# Gate_Drives.net
KiCad netlist of a schematic drawn in Altium Designer
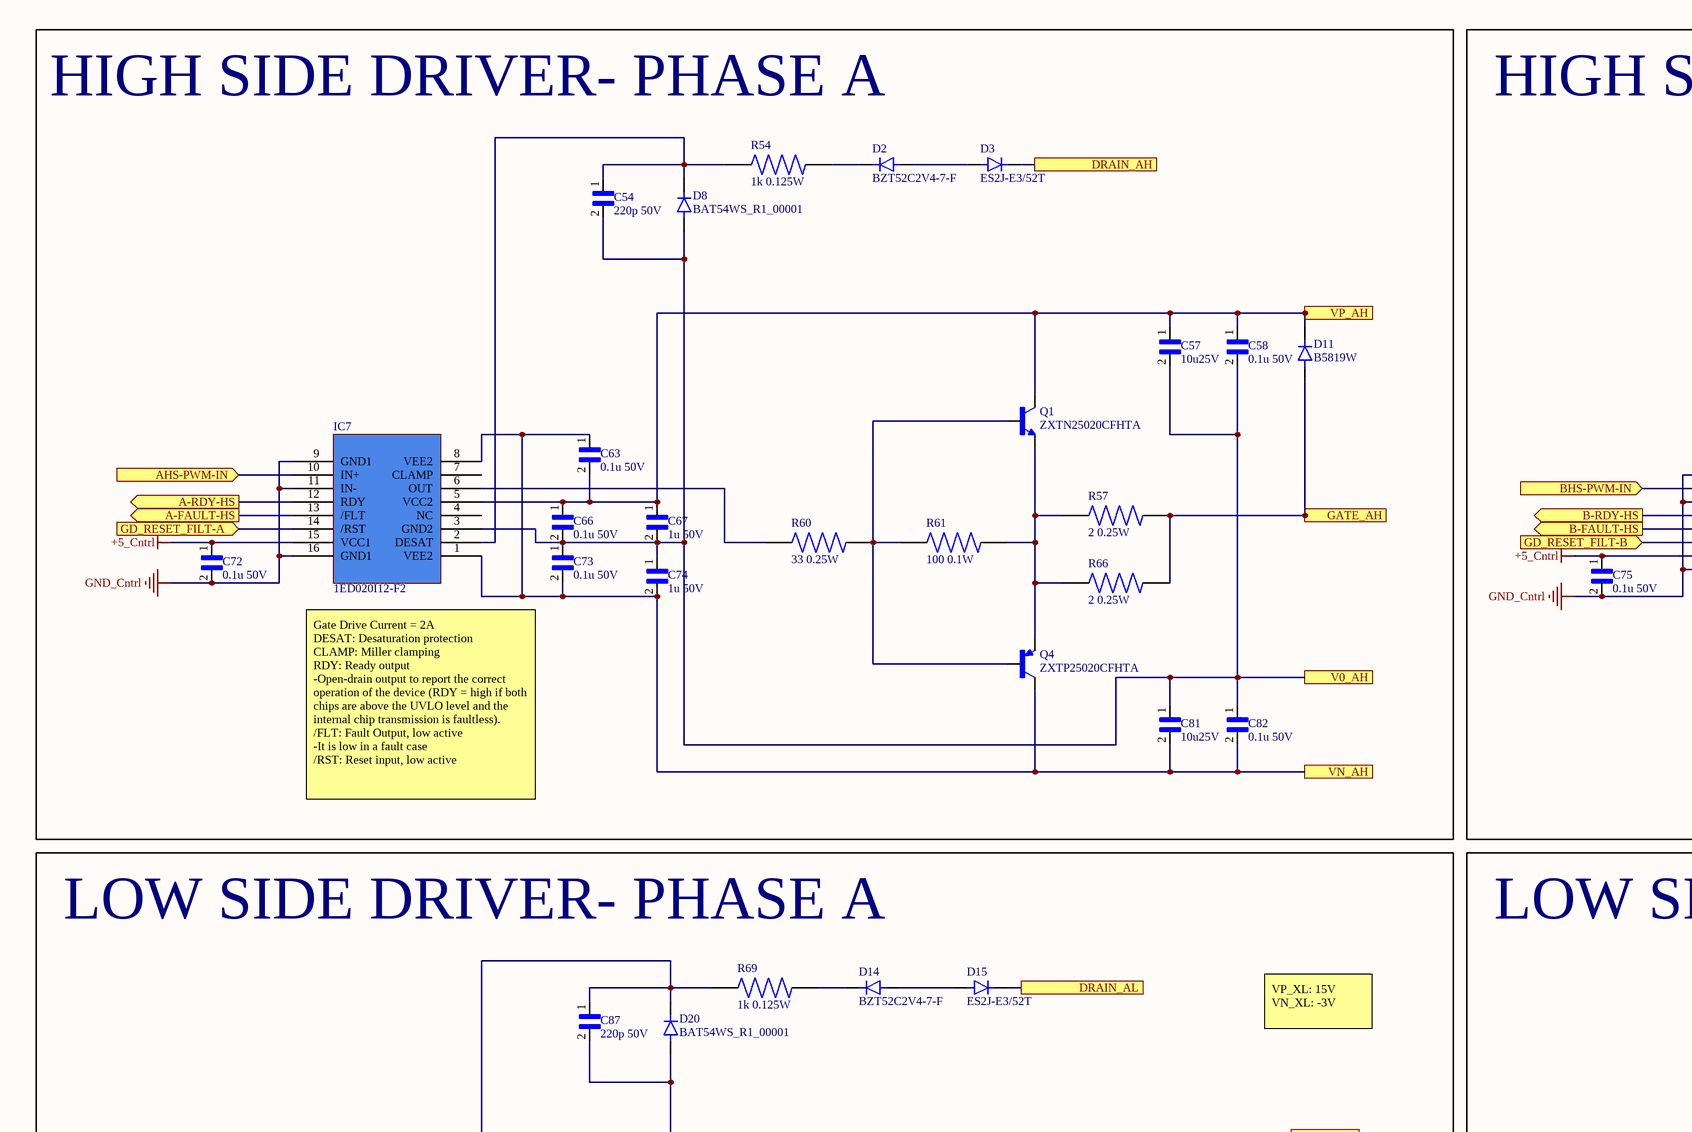
[diagram p0: Gate Drives.SchDoc, top left]
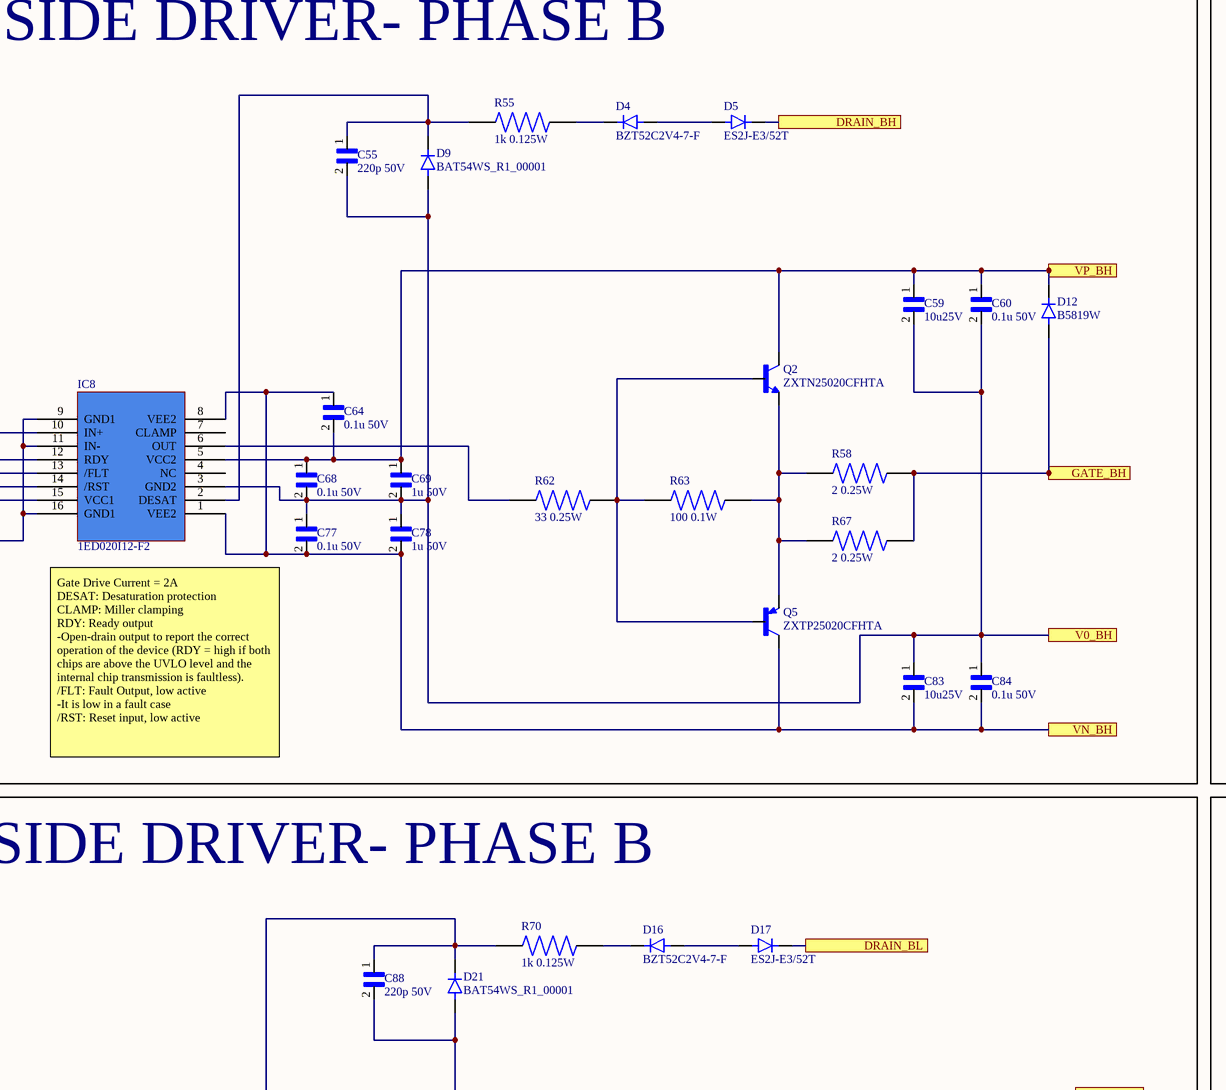
[diagram p1: Gate Drives.SchDoc, top middle]
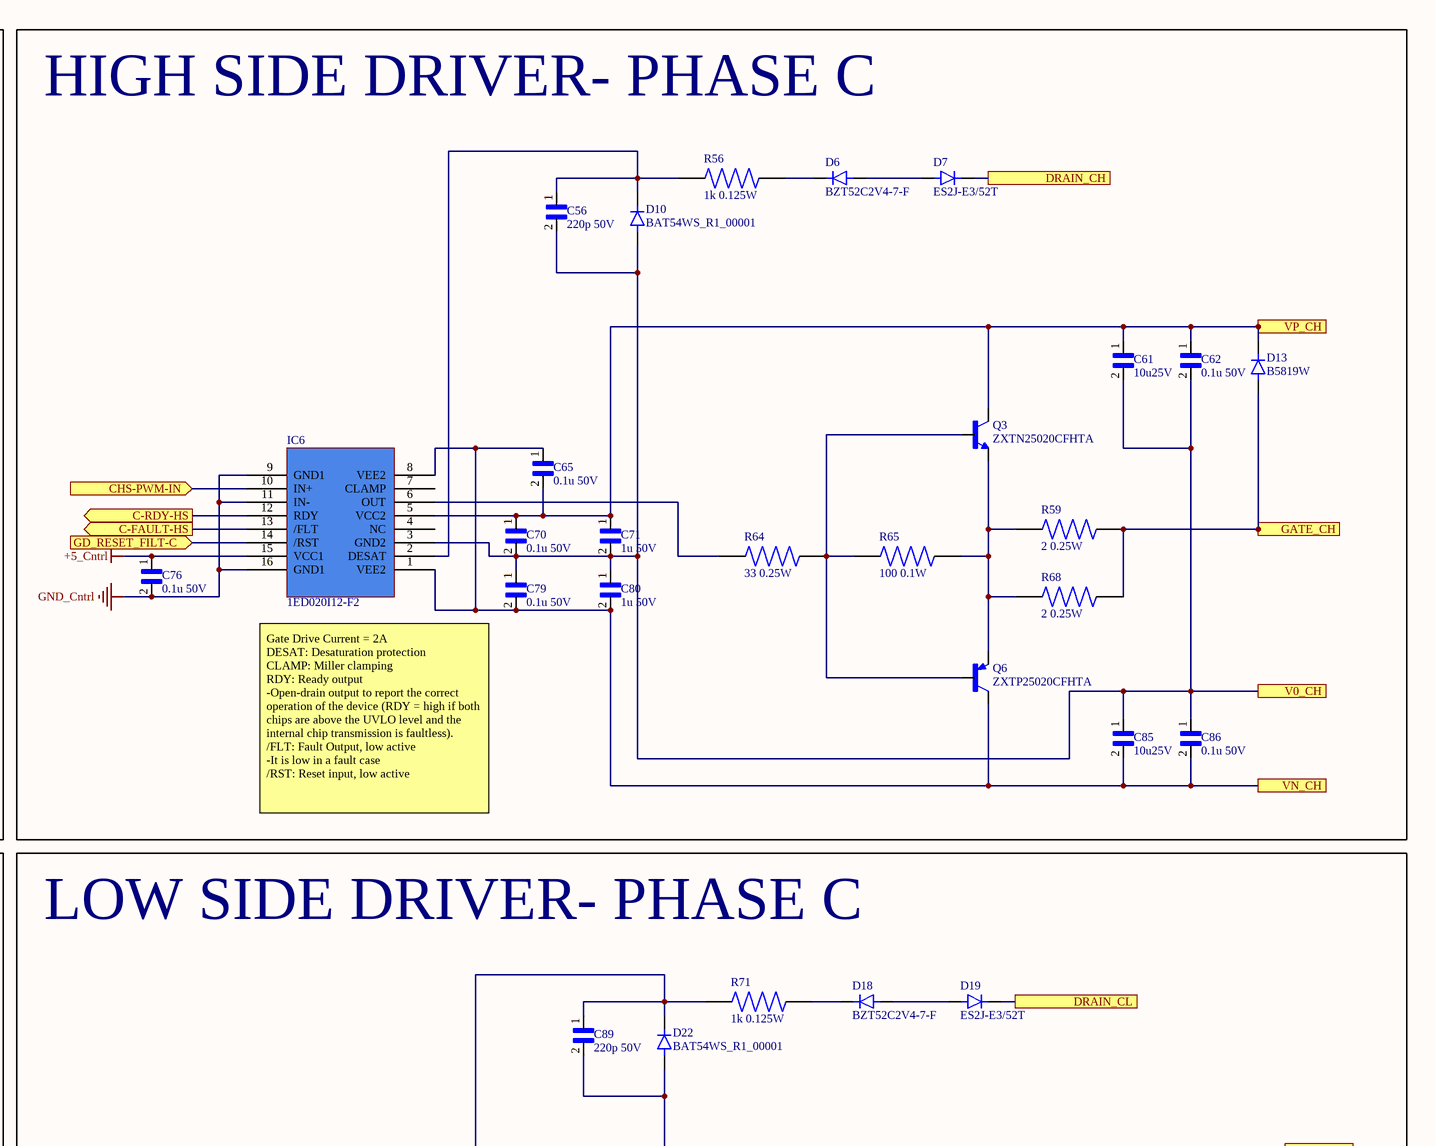
[diagram p2: Gate Drives.SchDoc, top right]
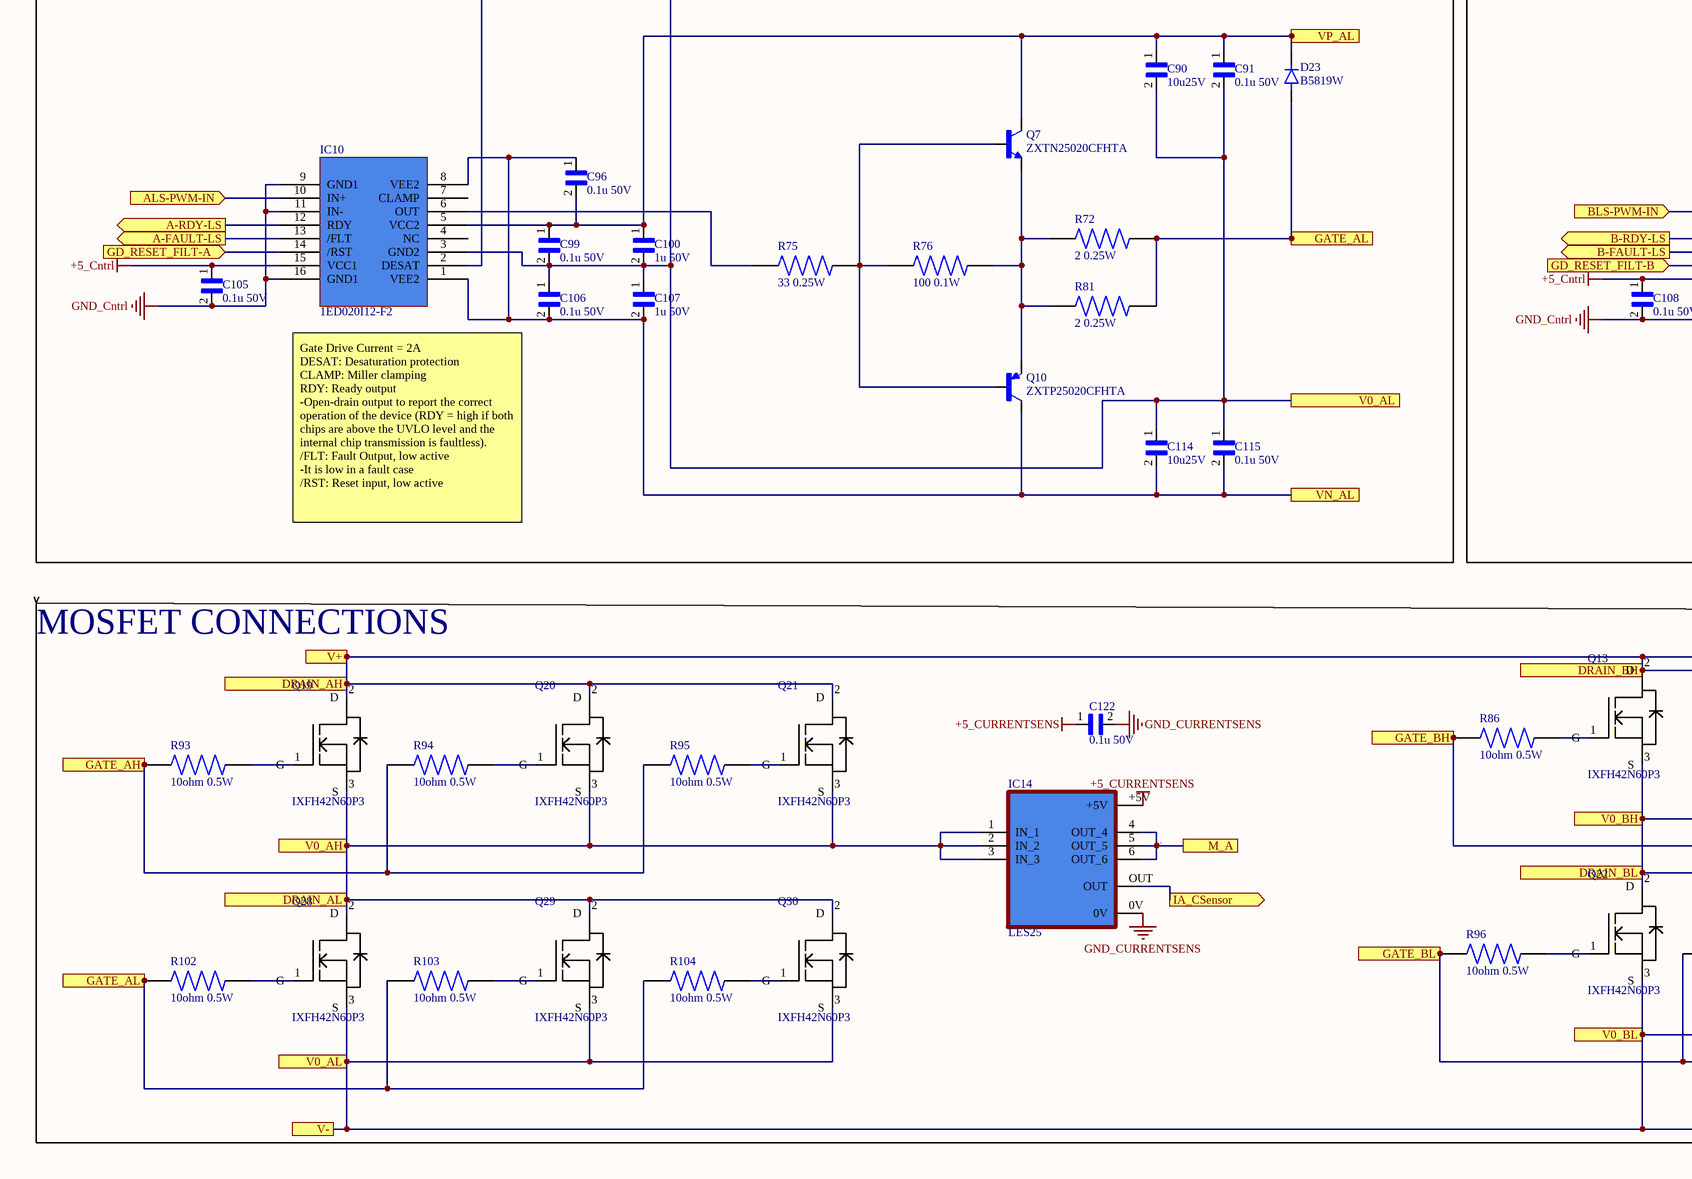
[diagram p3: Gate Drives.SchDoc, bottom left]
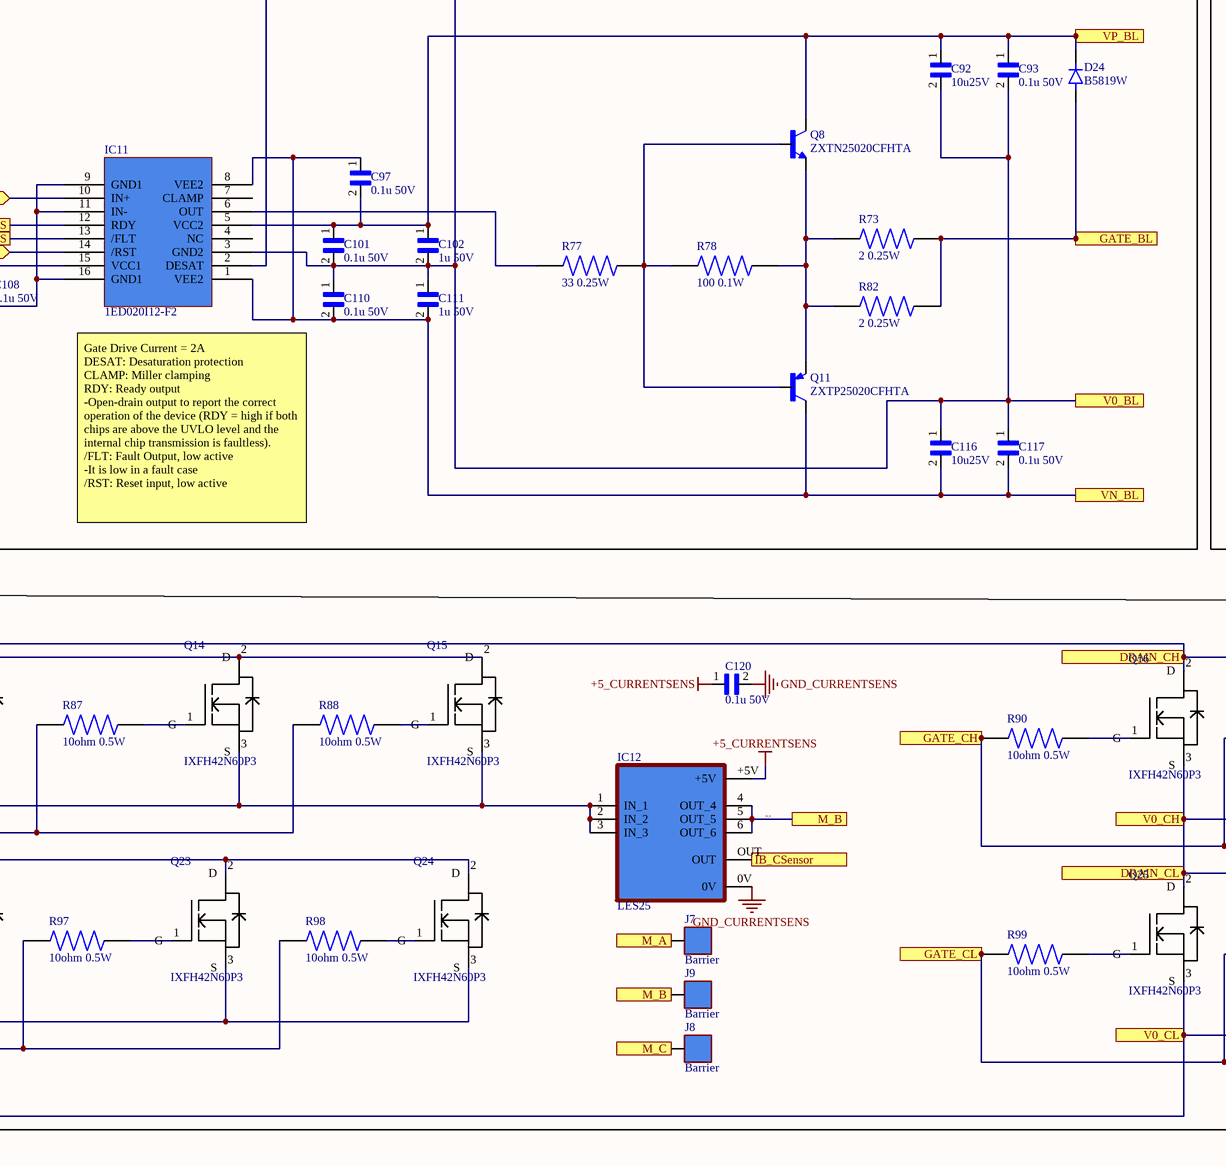
[diagram p4: Gate Drives.SchDoc, bottom middle]
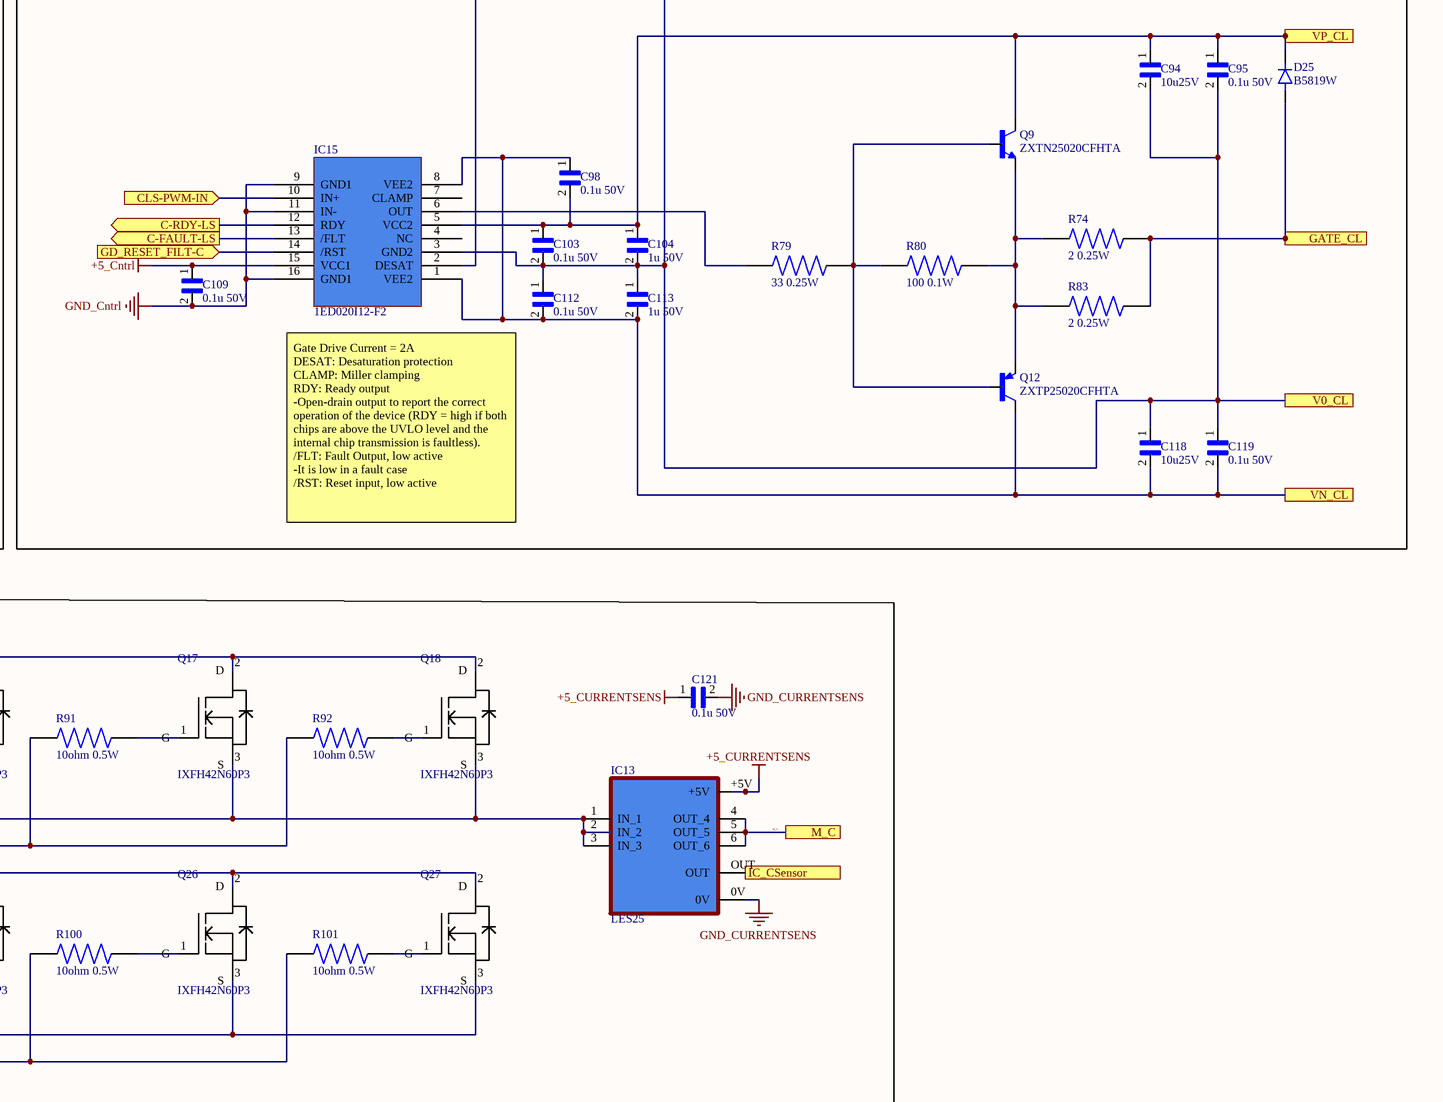
[diagram p5: Gate Drives.SchDoc, bottom right]

(export (version "E")
  (design (tool "Eeschema 10.0.6"))
  (components
    (comp (ref "C54") (value "220p 50V") (footprint "CAP0805") (libsource (lib "CAP0805") (part "CAP0805")))
    (comp (ref "C55") (value "220p 50V") (footprint "CAP0805") (libsource (lib "CAP0805") (part "CAP0805")))
    (comp (ref "C56") (value "220p 50V") (footprint "CAP0805") (libsource (lib "CAP0805") (part "CAP0805")))
    (comp (ref "C57") (value "10u25V") (footprint "CAP0805") (libsource (lib "CAP0805") (part "CAP0805")))
    (comp (ref "C58") (value "0.1u 50V") (footprint "CAP0805") (libsource (lib "CAP0805") (part "CAP0805")))
    (comp (ref "C59") (value "10u25V") (footprint "CAP0805") (libsource (lib "CAP0805") (part "CAP0805")))
    (comp (ref "C60") (value "0.1u 50V") (footprint "CAP0805") (libsource (lib "CAP0805") (part "CAP0805")))
    (comp (ref "C61") (value "10u25V") (footprint "CAP0805") (libsource (lib "CAP0805") (part "CAP0805")))
    (comp (ref "C62") (value "0.1u 50V") (footprint "CAP0805") (libsource (lib "CAP0805") (part "CAP0805")))
    (comp (ref "C63") (value "0.1u 50V") (footprint "CAP0805") (libsource (lib "CAP0805") (part "CAP0805")))
    (comp (ref "C64") (value "0.1u 50V") (footprint "CAP0805") (libsource (lib "CAP0805") (part "CAP0805")))
    (comp (ref "C65") (value "0.1u 50V") (footprint "CAP0805") (libsource (lib "CAP0805") (part "CAP0805")))
    (comp (ref "C66") (value "0.1u 50V") (footprint "CAP0805") (libsource (lib "CAP0805") (part "CAP0805")))
    (comp (ref "C67") (value "1u 50V") (footprint "CAP0805") (libsource (lib "CAP0805") (part "CAP0805")))
    (comp (ref "C68") (value "0.1u 50V") (footprint "CAP0805") (libsource (lib "CAP0805") (part "CAP0805")))
    (comp (ref "C69") (value "1u 50V") (footprint "CAP0805") (libsource (lib "CAP0805") (part "CAP0805")))
    (comp (ref "C70") (value "0.1u 50V") (footprint "CAP0805") (libsource (lib "CAP0805") (part "CAP0805")))
    (comp (ref "C71") (value "1u 50V") (footprint "CAP0805") (libsource (lib "CAP0805") (part "CAP0805")))
    (comp (ref "C72") (value "0.1u 50V") (footprint "CAP0805") (libsource (lib "CAP0805") (part "CAP0805")))
    (comp (ref "C73") (value "0.1u 50V") (footprint "CAP0805") (libsource (lib "CAP0805") (part "CAP0805")))
    (comp (ref "C74") (value "1u 50V") (footprint "CAP0805") (libsource (lib "CAP0805") (part "CAP0805")))
    (comp (ref "C75") (value "0.1u 50V") (footprint "CAP0805") (libsource (lib "CAP0805") (part "CAP0805")))
    (comp (ref "C76") (value "0.1u 50V") (footprint "CAP0805") (libsource (lib "CAP0805") (part "CAP0805")))
    (comp (ref "C77") (value "0.1u 50V") (footprint "CAP0805") (libsource (lib "CAP0805") (part "CAP0805")))
    (comp (ref "C78") (value "1u 50V") (footprint "CAP0805") (libsource (lib "CAP0805") (part "CAP0805")))
    (comp (ref "C79") (value "0.1u 50V") (footprint "CAP0805") (libsource (lib "CAP0805") (part "CAP0805")))
    (comp (ref "C80") (value "1u 50V") (footprint "CAP0805") (libsource (lib "CAP0805") (part "CAP0805")))
    (comp (ref "C81") (value "10u25V") (footprint "CAP0805") (libsource (lib "CAP0805") (part "CAP0805")))
    (comp (ref "C82") (value "0.1u 50V") (footprint "CAP0805") (libsource (lib "CAP0805") (part "CAP0805")))
    (comp (ref "C83") (value "10u25V") (footprint "CAP0805") (libsource (lib "CAP0805") (part "CAP0805")))
    (comp (ref "C84") (value "0.1u 50V") (footprint "CAP0805") (libsource (lib "CAP0805") (part "CAP0805")))
    (comp (ref "C85") (value "10u25V") (footprint "CAP0805") (libsource (lib "CAP0805") (part "CAP0805")))
    (comp (ref "C86") (value "0.1u 50V") (footprint "CAP0805") (libsource (lib "CAP0805") (part "CAP0805")))
    (comp (ref "C87") (value "220p 50V") (footprint "CAP0805") (libsource (lib "CAP0805") (part "CAP0805")))
    (comp (ref "C88") (value "220p 50V") (footprint "CAP0805") (libsource (lib "CAP0805") (part "CAP0805")))
    (comp (ref "C89") (value "220p 50V") (footprint "CAP0805") (libsource (lib "CAP0805") (part "CAP0805")))
    (comp (ref "C90") (value "10u25V") (footprint "CAP0805") (libsource (lib "CAP0805") (part "CAP0805")))
    (comp (ref "C91") (value "0.1u 50V") (footprint "CAP0805") (libsource (lib "CAP0805") (part "CAP0805")))
    (comp (ref "C92") (value "10u25V") (footprint "CAP0805") (libsource (lib "CAP0805") (part "CAP0805")))
    (comp (ref "C93") (value "0.1u 50V") (footprint "CAP0805") (libsource (lib "CAP0805") (part "CAP0805")))
    (comp (ref "C94") (value "10u25V") (footprint "CAP0805") (libsource (lib "CAP0805") (part "CAP0805")))
    (comp (ref "C95") (value "0.1u 50V") (footprint "CAP0805") (libsource (lib "CAP0805") (part "CAP0805")))
    (comp (ref "C96") (value "0.1u 50V") (footprint "CAP0805") (libsource (lib "CAP0805") (part "CAP0805")))
    (comp (ref "C97") (value "0.1u 50V") (footprint "CAP0805") (libsource (lib "CAP0805") (part "CAP0805")))
    (comp (ref "C98") (value "0.1u 50V") (footprint "CAP0805") (libsource (lib "CAP0805") (part "CAP0805")))
    (comp (ref "C99") (value "0.1u 50V") (footprint "CAP0805") (libsource (lib "CAP0805") (part "CAP0805")))
    (comp (ref "C100") (value "1u 50V") (footprint "CAP0805") (libsource (lib "CAP0805") (part "CAP0805")))
    (comp (ref "C101") (value "0.1u 50V") (footprint "CAP0805") (libsource (lib "CAP0805") (part "CAP0805")))
    (comp (ref "C102") (value "1u 50V") (footprint "CAP0805") (libsource (lib "CAP0805") (part "CAP0805")))
    (comp (ref "C103") (value "0.1u 50V") (footprint "CAP0805") (libsource (lib "CAP0805") (part "CAP0805")))
    (comp (ref "C104") (value "1u 50V") (footprint "CAP0805") (libsource (lib "CAP0805") (part "CAP0805")))
    (comp (ref "C105") (value "0.1u 50V") (footprint "CAP0805") (libsource (lib "CAP0805") (part "CAP0805")))
    (comp (ref "C106") (value "0.1u 50V") (footprint "CAP0805") (libsource (lib "CAP0805") (part "CAP0805")))
    (comp (ref "C107") (value "1u 50V") (footprint "CAP0805") (libsource (lib "CAP0805") (part "CAP0805")))
    (comp (ref "C108") (value "0.1u 50V") (footprint "CAP0805") (libsource (lib "CAP0805") (part "CAP0805")))
    (comp (ref "C109") (value "0.1u 50V") (footprint "CAP0805") (libsource (lib "CAP0805") (part "CAP0805")))
    (comp (ref "C110") (value "0.1u 50V") (footprint "CAP0805") (libsource (lib "CAP0805") (part "CAP0805")))
    (comp (ref "C111") (value "1u 50V") (footprint "CAP0805") (libsource (lib "CAP0805") (part "CAP0805")))
    (comp (ref "C112") (value "0.1u 50V") (footprint "CAP0805") (libsource (lib "CAP0805") (part "CAP0805")))
    (comp (ref "C113") (value "1u 50V") (footprint "CAP0805") (libsource (lib "CAP0805") (part "CAP0805")))
    (comp (ref "C114") (value "10u25V") (footprint "CAP0805") (libsource (lib "CAP0805") (part "CAP0805")))
    (comp (ref "C115") (value "0.1u 50V") (footprint "CAP0805") (libsource (lib "CAP0805") (part "CAP0805")))
    (comp (ref "C116") (value "10u25V") (footprint "CAP0805") (libsource (lib "CAP0805") (part "CAP0805")))
    (comp (ref "C117") (value "0.1u 50V") (footprint "CAP0805") (libsource (lib "CAP0805") (part "CAP0805")))
    (comp (ref "C118") (value "10u25V") (footprint "CAP0805") (libsource (lib "CAP0805") (part "CAP0805")))
    (comp (ref "C119") (value "0.1u 50V") (footprint "CAP0805") (libsource (lib "CAP0805") (part "CAP0805")))
    (comp (ref "C120") (value "0.1u 50V") (footprint "CAP0805") (libsource (lib "") (part "CAP0805_1")))
    (comp (ref "C121") (value "0.1u 50V") (footprint "CAP0805") (libsource (lib "") (part "CAP0805_1")))
    (comp (ref "C122") (value "0.1u 50V") (footprint "CAP0805") (libsource (lib "") (part "CAP0805_1")))
    (comp (ref "D2")
      (value "BZT52C2V4-7-F")
      (footprint "BZT52C2V4-7-F")
      (libsource (lib "BZT52C2V4-7-F") (part "BZT52C2V4-7-F"))
    )
    (comp (ref "D3")
      (value "ES2J-E3/52T")
      (footprint "ES2J-E3/52T")
      (libsource (lib "ES2J-E3 52T") (part "ES2J-E3/52T"))
    )
    (comp (ref "D4")
      (value "BZT52C2V4-7-F")
      (footprint "BZT52C2V4-7-F")
      (libsource (lib "BZT52C2V4-7-F") (part "BZT52C2V4-7-F"))
    )
    (comp (ref "D5")
      (value "ES2J-E3/52T")
      (footprint "ES2J-E3/52T")
      (libsource (lib "ES2J-E3 52T") (part "ES2J-E3/52T"))
    )
    (comp (ref "D6")
      (value "BZT52C2V4-7-F")
      (footprint "BZT52C2V4-7-F")
      (libsource (lib "BZT52C2V4-7-F") (part "BZT52C2V4-7-F"))
    )
    (comp (ref "D7")
      (value "ES2J-E3/52T")
      (footprint "ES2J-E3/52T")
      (libsource (lib "ES2J-E3 52T") (part "ES2J-E3/52T"))
    )
    (comp (ref "D8")
      (value "BAT54WS_R1_00001")
      (footprint "BAT54WS_R1_00001")
      (libsource (lib "BAT54WS_R1_00001") (part "BAT54WS_R1_00001"))
    )
    (comp (ref "D9")
      (value "BAT54WS_R1_00001")
      (footprint "BAT54WS_R1_00001")
      (libsource (lib "BAT54WS_R1_00001") (part "BAT54WS_R1_00001"))
    )
    (comp (ref "D10")
      (value "BAT54WS_R1_00001")
      (footprint "BAT54WS_R1_00001")
      (libsource (lib "BAT54WS_R1_00001") (part "BAT54WS_R1_00001"))
    )
    (comp (ref "D11")
      (value "B5819W")
      (footprint "BZT52C2V4-7-F")
      (description "DIODE SCHOTTKY 1A 40V SOD123")
      (libsource (lib "B5819W") (part "B5819W"))
    )
    (comp (ref "D12")
      (value "B5819W")
      (footprint "BZT52C2V4-7-F")
      (description "DIODE SCHOTTKY 1A 40V SOD123")
      (libsource (lib "B5819W") (part "B5819W"))
    )
    (comp (ref "D13")
      (value "B5819W")
      (footprint "BZT52C2V4-7-F")
      (description "DIODE SCHOTTKY 1A 40V SOD123")
      (libsource (lib "B5819W") (part "B5819W"))
    )
    (comp (ref "D14")
      (value "BZT52C2V4-7-F")
      (footprint "BZT52C2V4-7-F")
      (libsource (lib "BZT52C2V4-7-F") (part "BZT52C2V4-7-F"))
    )
    (comp (ref "D15")
      (value "ES2J-E3/52T")
      (footprint "ES2J-E3/52T")
      (libsource (lib "ES2J-E3 52T") (part "ES2J-E3/52T"))
    )
    (comp (ref "D16")
      (value "BZT52C2V4-7-F")
      (footprint "BZT52C2V4-7-F")
      (libsource (lib "BZT52C2V4-7-F") (part "BZT52C2V4-7-F"))
    )
    (comp (ref "D17")
      (value "ES2J-E3/52T")
      (footprint "ES2J-E3/52T")
      (libsource (lib "ES2J-E3 52T") (part "ES2J-E3/52T"))
    )
    (comp (ref "D18")
      (value "BZT52C2V4-7-F")
      (footprint "BZT52C2V4-7-F")
      (libsource (lib "BZT52C2V4-7-F") (part "BZT52C2V4-7-F"))
    )
    (comp (ref "D19")
      (value "ES2J-E3/52T")
      (footprint "ES2J-E3/52T")
      (libsource (lib "ES2J-E3 52T") (part "ES2J-E3/52T"))
    )
    (comp (ref "D20")
      (value "BAT54WS_R1_00001")
      (footprint "BAT54WS_R1_00001")
      (libsource (lib "BAT54WS_R1_00001") (part "BAT54WS_R1_00001"))
    )
    (comp (ref "D21")
      (value "BAT54WS_R1_00001")
      (footprint "BAT54WS_R1_00001")
      (libsource (lib "BAT54WS_R1_00001") (part "BAT54WS_R1_00001"))
    )
    (comp (ref "D22")
      (value "BAT54WS_R1_00001")
      (footprint "BAT54WS_R1_00001")
      (libsource (lib "BAT54WS_R1_00001") (part "BAT54WS_R1_00001"))
    )
    (comp (ref "D23")
      (value "B5819W")
      (footprint "BZT52C2V4-7-F")
      (description "DIODE SCHOTTKY 1A 40V SOD123")
      (libsource (lib "B5819W") (part "B5819W"))
    )
    (comp (ref "D24")
      (value "B5819W")
      (footprint "BZT52C2V4-7-F")
      (description "DIODE SCHOTTKY 1A 40V SOD123")
      (libsource (lib "B5819W") (part "B5819W"))
    )
    (comp (ref "D25")
      (value "B5819W")
      (footprint "BZT52C2V4-7-F")
      (description "DIODE SCHOTTKY 1A 40V SOD123")
      (libsource (lib "B5819W") (part "B5819W"))
    )
    (comp (ref "IC6")
      (value "1ED020I12-F2")
      (footprint "SOIC127P1028X264-16N")
      (libsource (lib "1ED020I12-F2v2") (part "1ED020I12-F2"))
    )
    (comp (ref "IC7")
      (value "1ED020I12-F2")
      (footprint "SOIC127P1028X264-16N")
      (libsource (lib "1ED020I12-F2v2") (part "1ED020I12-F2"))
    )
    (comp (ref "IC8")
      (value "1ED020I12-F2")
      (footprint "SOIC127P1028X264-16N")
      (libsource (lib "1ED020I12-F2v2") (part "1ED020I12-F2"))
    )
    (comp (ref "IC10")
      (value "1ED020I12-F2")
      (footprint "SOIC127P1028X264-16N")
      (libsource (lib "1ED020I12-F2v2") (part "1ED020I12-F2"))
    )
    (comp (ref "IC11")
      (value "1ED020I12-F2")
      (footprint "SOIC127P1028X264-16N")
      (libsource (lib "1ED020I12-F2v2") (part "1ED020I12-F2"))
    )
    (comp (ref "IC12") (value "LES25") (footprint "LTS25") (libsource (lib "LES25") (part "LES25")))
    (comp (ref "IC13") (value "LES25") (footprint "LTS25") (libsource (lib "LES25") (part "LES25")))
    (comp (ref "IC14") (value "LES25") (footprint "LTS25") (libsource (lib "LES25") (part "LES25")))
    (comp (ref "IC15")
      (value "1ED020I12-F2")
      (footprint "SOIC127P1028X264-16N")
      (libsource (lib "1ED020I12-F2v2") (part "1ED020I12-F2"))
    )
    (comp (ref "J7") (value "Barrier") (footprint "Barrier") (libsource (lib "Barrier") (part "Barrier")))
    (comp (ref "J8") (value "Barrier") (footprint "Barrier") (libsource (lib "Barrier") (part "Barrier")))
    (comp (ref "J9") (value "Barrier") (footprint "Barrier") (libsource (lib "Barrier") (part "Barrier")))
    (comp (ref "Q1")
      (value "ZXTN25020CFHTA")
      (footprint "SOT23")
      (description "NPN 4.5A SOT23")
      (libsource (lib "ZXTN25020CFHTA") (part "ZXTN25020CFHTA"))
    )
    (comp (ref "Q2")
      (value "ZXTN25020CFHTA")
      (footprint "SOT23")
      (description "NPN 4.5A SOT23")
      (libsource (lib "ZXTN25020CFHTA") (part "ZXTN25020CFHTA"))
    )
    (comp (ref "Q3")
      (value "ZXTN25020CFHTA")
      (footprint "SOT23")
      (description "NPN 4.5A SOT23")
      (libsource (lib "ZXTN25020CFHTA") (part "ZXTN25020CFHTA"))
    )
    (comp (ref "Q4")
      (value "ZXTP25020CFHTA")
      (footprint "SOT23")
      (description "PNP 4A SOT23")
      (libsource (lib "ZXTP25020CFHTA") (part "ZXTP25020CFHTA"))
    )
    (comp (ref "Q5")
      (value "ZXTP25020CFHTA")
      (footprint "SOT23")
      (description "PNP 4A SOT23")
      (libsource (lib "ZXTP25020CFHTA") (part "ZXTP25020CFHTA"))
    )
    (comp (ref "Q6")
      (value "ZXTP25020CFHTA")
      (footprint "SOT23")
      (description "PNP 4A SOT23")
      (libsource (lib "ZXTP25020CFHTA") (part "ZXTP25020CFHTA"))
    )
    (comp (ref "Q7")
      (value "ZXTN25020CFHTA")
      (footprint "SOT23")
      (description "NPN 4.5A SOT23")
      (libsource (lib "ZXTN25020CFHTA") (part "ZXTN25020CFHTA"))
    )
    (comp (ref "Q8")
      (value "ZXTN25020CFHTA")
      (footprint "SOT23")
      (description "NPN 4.5A SOT23")
      (libsource (lib "ZXTN25020CFHTA") (part "ZXTN25020CFHTA"))
    )
    (comp (ref "Q9")
      (value "ZXTN25020CFHTA")
      (footprint "SOT23")
      (description "NPN 4.5A SOT23")
      (libsource (lib "ZXTN25020CFHTA") (part "ZXTN25020CFHTA"))
    )
    (comp (ref "Q10")
      (value "ZXTP25020CFHTA")
      (footprint "SOT23")
      (description "PNP 4A SOT23")
      (libsource (lib "ZXTP25020CFHTA") (part "ZXTP25020CFHTA"))
    )
    (comp (ref "Q11")
      (value "ZXTP25020CFHTA")
      (footprint "SOT23")
      (description "PNP 4A SOT23")
      (libsource (lib "ZXTP25020CFHTA") (part "ZXTP25020CFHTA"))
    )
    (comp (ref "Q12")
      (value "ZXTP25020CFHTA")
      (footprint "SOT23")
      (description "PNP 4A SOT23")
      (libsource (lib "ZXTP25020CFHTA") (part "ZXTP25020CFHTA"))
    )
    (comp (ref "Q13")
      (value "IXFH42N60P3")
      (footprint "IXFH42N60P3_v4")
      (libsource (lib "IXFH42N60P3_lastVersion") (part "IXFH42N60P3"))
    )
    (comp (ref "Q14")
      (value "IXFH42N60P3")
      (footprint "IXFH42N60P3_v4")
      (libsource (lib "IXFH42N60P3_lastVersion") (part "IXFH42N60P3"))
    )
    (comp (ref "Q15")
      (value "IXFH42N60P3")
      (footprint "IXFH42N60P3_v4")
      (libsource (lib "IXFH42N60P3_lastVersion") (part "IXFH42N60P3"))
    )
    (comp (ref "Q16")
      (value "IXFH42N60P3")
      (footprint "IXFH42N60P3_v4")
      (libsource (lib "IXFH42N60P3_lastVersion") (part "IXFH42N60P3"))
    )
    (comp (ref "Q17")
      (value "IXFH42N60P3")
      (footprint "IXFH42N60P3_v4")
      (libsource (lib "IXFH42N60P3_lastVersion") (part "IXFH42N60P3"))
    )
    (comp (ref "Q18")
      (value "IXFH42N60P3")
      (footprint "IXFH42N60P3_v4")
      (libsource (lib "IXFH42N60P3_lastVersion") (part "IXFH42N60P3"))
    )
    (comp (ref "Q19")
      (value "IXFH42N60P3")
      (footprint "IXFH42N60P3_v4")
      (libsource (lib "IXFH42N60P3_lastVersion") (part "IXFH42N60P3"))
    )
    (comp (ref "Q20")
      (value "IXFH42N60P3")
      (footprint "IXFH42N60P3_v4")
      (libsource (lib "IXFH42N60P3_lastVersion") (part "IXFH42N60P3"))
    )
    (comp (ref "Q21")
      (value "IXFH42N60P3")
      (footprint "IXFH42N60P3_v4")
      (libsource (lib "IXFH42N60P3_lastVersion") (part "IXFH42N60P3"))
    )
    (comp (ref "Q22")
      (value "IXFH42N60P3")
      (footprint "IXFH42N60P3_v4")
      (libsource (lib "IXFH42N60P3_lastVersion") (part "IXFH42N60P3"))
    )
    (comp (ref "Q23")
      (value "IXFH42N60P3")
      (footprint "IXFH42N60P3_v4")
      (libsource (lib "IXFH42N60P3_lastVersion") (part "IXFH42N60P3"))
    )
    (comp (ref "Q24")
      (value "IXFH42N60P3")
      (footprint "IXFH42N60P3_v4")
      (libsource (lib "IXFH42N60P3_lastVersion") (part "IXFH42N60P3"))
    )
    (comp (ref "Q25")
      (value "IXFH42N60P3")
      (footprint "IXFH42N60P3_v4")
      (libsource (lib "IXFH42N60P3_lastVersion") (part "IXFH42N60P3"))
    )
    (comp (ref "Q26")
      (value "IXFH42N60P3")
      (footprint "IXFH42N60P3_v4")
      (libsource (lib "IXFH42N60P3_lastVersion") (part "IXFH42N60P3"))
    )
    (comp (ref "Q27")
      (value "IXFH42N60P3")
      (footprint "IXFH42N60P3_v4")
      (libsource (lib "IXFH42N60P3_lastVersion") (part "IXFH42N60P3"))
    )
    (comp (ref "Q28")
      (value "IXFH42N60P3")
      (footprint "IXFH42N60P3_v4")
      (libsource (lib "IXFH42N60P3_lastVersion") (part "IXFH42N60P3"))
    )
    (comp (ref "Q29")
      (value "IXFH42N60P3")
      (footprint "IXFH42N60P3_v4")
      (libsource (lib "IXFH42N60P3_lastVersion") (part "IXFH42N60P3"))
    )
    (comp (ref "Q30")
      (value "IXFH42N60P3")
      (footprint "IXFH42N60P3_v4")
      (libsource (lib "IXFH42N60P3_lastVersion") (part "IXFH42N60P3"))
    )
    (comp (ref "R54") (value "1k 0.125W") (footprint "RES0805") (libsource (lib "RES0805") (part "RES0805")))
    (comp (ref "R55") (value "1k 0.125W") (footprint "RES0805") (libsource (lib "RES0805") (part "RES0805")))
    (comp (ref "R56") (value "1k 0.125W") (footprint "RES0805") (libsource (lib "RES0805") (part "RES0805")))
    (comp (ref "R57") (value "2 0.25W") (footprint "RES0805") (libsource (lib "RES0805") (part "RES0805")))
    (comp (ref "R58") (value "2 0.25W") (footprint "RES0805") (libsource (lib "RES0805") (part "RES0805")))
    (comp (ref "R59") (value "2 0.25W") (footprint "RES0805") (libsource (lib "RES0805") (part "RES0805")))
    (comp (ref "R60") (value "33 0.25W") (footprint "RES0805") (libsource (lib "RES0805") (part "RES0805")))
    (comp (ref "R61") (value "100 0.1W") (footprint "RES0805") (libsource (lib "RES0805") (part "RES0805")))
    (comp (ref "R62") (value "33 0.25W") (footprint "RES0805") (libsource (lib "RES0805") (part "RES0805")))
    (comp (ref "R63") (value "100 0.1W") (footprint "RES0805") (libsource (lib "RES0805") (part "RES0805")))
    (comp (ref "R64") (value "33 0.25W") (footprint "RES0805") (libsource (lib "RES0805") (part "RES0805")))
    (comp (ref "R65") (value "100 0.1W") (footprint "RES0805") (libsource (lib "RES0805") (part "RES0805")))
    (comp (ref "R66") (value "2 0.25W") (footprint "RES0805") (libsource (lib "RES0805") (part "RES0805")))
    (comp (ref "R67") (value "2 0.25W") (footprint "RES0805") (libsource (lib "RES0805") (part "RES0805")))
    (comp (ref "R68") (value "2 0.25W") (footprint "RES0805") (libsource (lib "RES0805") (part "RES0805")))
    (comp (ref "R69") (value "1k 0.125W") (footprint "RES0805") (libsource (lib "RES0805") (part "RES0805")))
    (comp (ref "R70") (value "1k 0.125W") (footprint "RES0805") (libsource (lib "RES0805") (part "RES0805")))
    (comp (ref "R71") (value "1k 0.125W") (footprint "RES0805") (libsource (lib "RES0805") (part "RES0805")))
    (comp (ref "R72") (value "2 0.25W") (footprint "RES0805") (libsource (lib "RES0805") (part "RES0805")))
    (comp (ref "R73") (value "2 0.25W") (footprint "RES0805") (libsource (lib "RES0805") (part "RES0805")))
    (comp (ref "R74") (value "2 0.25W") (footprint "RES0805") (libsource (lib "RES0805") (part "RES0805")))
    (comp (ref "R75") (value "33 0.25W") (footprint "RES0805") (libsource (lib "RES0805") (part "RES0805")))
    (comp (ref "R76") (value "100 0.1W") (footprint "RES0805") (libsource (lib "RES0805") (part "RES0805")))
    (comp (ref "R77") (value "33 0.25W") (footprint "RES0805") (libsource (lib "RES0805") (part "RES0805")))
    (comp (ref "R78") (value "100 0.1W") (footprint "RES0805") (libsource (lib "RES0805") (part "RES0805")))
    (comp (ref "R79") (value "33 0.25W") (footprint "RES0805") (libsource (lib "RES0805") (part "RES0805")))
    (comp (ref "R80") (value "100 0.1W") (footprint "RES0805") (libsource (lib "RES0805") (part "RES0805")))
    (comp (ref "R81") (value "2 0.25W") (footprint "RES0805") (libsource (lib "RES0805") (part "RES0805")))
    (comp (ref "R82") (value "2 0.25W") (footprint "RES0805") (libsource (lib "RES0805") (part "RES0805")))
    (comp (ref "R83") (value "2 0.25W") (footprint "RES0805") (libsource (lib "RES0805") (part "RES0805")))
    (comp (ref "R86")
      (value "10ohm 0.5W")
      (footprint "1206RES")
      (description "1206 RES")
      (libsource (lib "1206RES") (part "249k 1206"))
    )
    (comp (ref "R87")
      (value "10ohm 0.5W")
      (footprint "1206RES")
      (description "1206 RES")
      (libsource (lib "1206RES") (part "249k 1206"))
    )
    (comp (ref "R88")
      (value "10ohm 0.5W")
      (footprint "1206RES")
      (description "1206 RES")
      (libsource (lib "1206RES") (part "249k 1206"))
    )
    (comp (ref "R90")
      (value "10ohm 0.5W")
      (footprint "1206RES")
      (description "1206 RES")
      (libsource (lib "1206RES") (part "249k 1206"))
    )
    (comp (ref "R91")
      (value "10ohm 0.5W")
      (footprint "1206RES")
      (description "1206 RES")
      (libsource (lib "1206RES") (part "249k 1206"))
    )
    (comp (ref "R92")
      (value "10ohm 0.5W")
      (footprint "1206RES")
      (description "1206 RES")
      (libsource (lib "1206RES") (part "249k 1206"))
    )
    (comp (ref "R93")
      (value "10ohm 0.5W")
      (footprint "1206RES")
      (description "1206 RES")
      (libsource (lib "1206RES") (part "249k 1206"))
    )
    (comp (ref "R94")
      (value "10ohm 0.5W")
      (footprint "1206RES")
      (description "1206 RES")
      (libsource (lib "1206RES") (part "249k 1206"))
    )
    (comp (ref "R95")
      (value "10ohm 0.5W")
      (footprint "1206RES")
      (description "1206 RES")
      (libsource (lib "1206RES") (part "249k 1206"))
    )
    (comp (ref "R96")
      (value "10ohm 0.5W")
      (footprint "1206RES")
      (description "1206 RES")
      (libsource (lib "1206RES") (part "249k 1206"))
    )
    (comp (ref "R97")
      (value "10ohm 0.5W")
      (footprint "1206RES")
      (description "1206 RES")
      (libsource (lib "1206RES") (part "249k 1206"))
    )
    (comp (ref "R98")
      (value "10ohm 0.5W")
      (footprint "1206RES")
      (description "1206 RES")
      (libsource (lib "1206RES") (part "249k 1206"))
    )
    (comp (ref "R99")
      (value "10ohm 0.5W")
      (footprint "1206RES")
      (description "1206 RES")
      (libsource (lib "1206RES") (part "249k 1206"))
    )
    (comp (ref "R100")
      (value "10ohm 0.5W")
      (footprint "1206RES")
      (description "1206 RES")
      (libsource (lib "1206RES") (part "249k 1206"))
    )
    (comp (ref "R101")
      (value "10ohm 0.5W")
      (footprint "1206RES")
      (description "1206 RES")
      (libsource (lib "1206RES") (part "249k 1206"))
    )
    (comp (ref "R102")
      (value "10ohm 0.5W")
      (footprint "1206RES")
      (description "1206 RES")
      (libsource (lib "1206RES") (part "249k 1206"))
    )
    (comp (ref "R103")
      (value "10ohm 0.5W")
      (footprint "1206RES")
      (description "1206 RES")
      (libsource (lib "1206RES") (part "249k 1206"))
    )
    (comp (ref "R104")
      (value "10ohm 0.5W")
      (footprint "1206RES")
      (description "1206 RES")
      (libsource (lib "1206RES") (part "249k 1206"))
    )
  )
  (nets
    (net (code "1") (name "+5_CURRENTSENS") (class "Default")
      (node (ref "C120") (pin "1") (pinfunction "1_1") (pintype "passive"))
      (node (ref "C121") (pin "1") (pinfunction "1_1") (pintype "passive"))
      (node (ref "C122") (pin "1") (pinfunction "1_1") (pintype "passive"))
      (node (ref "IC12") (pin "+5V") (pinfunction "+5V_+5V") (pintype "power_in"))
      (node (ref "IC13") (pin "+5V") (pinfunction "+5V_+5V") (pintype "power_in"))
      (node (ref "IC14") (pin "+5V") (pinfunction "+5V_+5V") (pintype "power_in"))
    )
    (net (code "2") (name "+5_Cntrl") (class "Default")
      (node (ref "C105") (pin "1") (pinfunction "1_1") (pintype "passive"))
      (node (ref "C108") (pin "1") (pinfunction "1_1") (pintype "passive"))
      (node (ref "C109") (pin "1") (pinfunction "1_1") (pintype "passive"))
      (node (ref "C72") (pin "1") (pinfunction "1_1") (pintype "passive"))
      (node (ref "C75") (pin "1") (pinfunction "1_1") (pintype "passive"))
      (node (ref "C76") (pin "1") (pinfunction "1_1") (pintype "passive"))
      (node (ref "IC10") (pin "15") (pinfunction "VCC1_15") (pintype "passive"))
      (node (ref "IC11") (pin "15") (pinfunction "VCC1_15") (pintype "passive"))
      (node (ref "IC15") (pin "15") (pinfunction "VCC1_15") (pintype "passive"))
      (node (ref "IC6") (pin "15") (pinfunction "VCC1_15") (pintype "passive"))
      (node (ref "IC7") (pin "15") (pinfunction "VCC1_15") (pintype "passive"))
      (node (ref "IC8") (pin "15") (pinfunction "VCC1_15") (pintype "passive"))
    )
    (net (code "3") (name "/A-FAULT-HS") (class "Default")
      (node (ref "IC7") (pin "13") (pinfunction "/FLT_13") (pintype "passive"))
    )
    (net (code "4") (name "/A-FAULT-LS") (class "Default")
      (node (ref "IC10") (pin "13") (pinfunction "/FLT_13") (pintype "passive"))
    )
    (net (code "5") (name "/A-RDY-HS") (class "Default")
      (node (ref "IC7") (pin "12") (pinfunction "RDY_12") (pintype "passive"))
    )
    (net (code "6") (name "/A-RDY-LS") (class "Default")
      (node (ref "IC10") (pin "12") (pinfunction "RDY_12") (pintype "passive"))
    )
    (net (code "7") (name "/AHS-PWM-IN") (class "Default")
      (node (ref "IC7") (pin "10") (pinfunction "IN+_10") (pintype "passive"))
    )
    (net (code "8") (name "/ALS-PWM-IN") (class "Default")
      (node (ref "IC10") (pin "10") (pinfunction "IN+_10") (pintype "passive"))
    )
    (net (code "9") (name "/B-FAULT-HS") (class "Default")
      (node (ref "IC8") (pin "13") (pinfunction "/FLT_13") (pintype "passive"))
    )
    (net (code "10") (name "/B-FAULT-LS") (class "Default")
      (node (ref "IC11") (pin "13") (pinfunction "/FLT_13") (pintype "passive"))
    )
    (net (code "11") (name "/B-RDY-HS") (class "Default")
      (node (ref "IC8") (pin "12") (pinfunction "RDY_12") (pintype "passive"))
    )
    (net (code "12") (name "/B-RDY-LS") (class "Default")
      (node (ref "IC11") (pin "12") (pinfunction "RDY_12") (pintype "passive"))
    )
    (net (code "13") (name "/BHS-PWM-IN") (class "Default")
      (node (ref "IC8") (pin "10") (pinfunction "IN+_10") (pintype "passive"))
    )
    (net (code "14") (name "/BLS-PWM-IN") (class "Default")
      (node (ref "IC11") (pin "10") (pinfunction "IN+_10") (pintype "passive"))
    )
    (net (code "15") (name "/C-FAULT-HS") (class "Default")
      (node (ref "IC6") (pin "13") (pinfunction "/FLT_13") (pintype "passive"))
    )
    (net (code "16") (name "/C-FAULT-LS") (class "Default")
      (node (ref "IC15") (pin "13") (pinfunction "/FLT_13") (pintype "passive"))
    )
    (net (code "17") (name "/C-RDY-HS") (class "Default")
      (node (ref "IC6") (pin "12") (pinfunction "RDY_12") (pintype "passive"))
    )
    (net (code "18") (name "/C-RDY-LS") (class "Default")
      (node (ref "IC15") (pin "12") (pinfunction "RDY_12") (pintype "passive"))
    )
    (net (code "19") (name "/CHS-PWM-IN") (class "Default")
      (node (ref "IC6") (pin "10") (pinfunction "IN+_10") (pintype "passive"))
    )
    (net (code "20") (name "/CLS-PWM-IN") (class "Default")
      (node (ref "IC15") (pin "10") (pinfunction "IN+_10") (pintype "passive"))
    )
    (net (code "21") (name "/DRAIN_AH") (class "Default")
      (node (ref "D3") (pin "1") (pinfunction "Cathode_1") (pintype "passive"))
      (node (ref "D5") (pin "1") (pinfunction "Cathode_1") (pintype "passive"))
      (node (ref "D7") (pin "1") (pinfunction "Cathode_1") (pintype "passive"))
      (node (ref "Q13") (pin "2") (pinfunction "D_2") (pintype "passive"))
      (node (ref "Q14") (pin "2") (pinfunction "D_2") (pintype "passive"))
      (node (ref "Q15") (pin "2") (pinfunction "D_2") (pintype "passive"))
      (node (ref "Q16") (pin "2") (pinfunction "D_2") (pintype "passive"))
      (node (ref "Q17") (pin "2") (pinfunction "D_2") (pintype "passive"))
      (node (ref "Q18") (pin "2") (pinfunction "D_2") (pintype "passive"))
      (node (ref "Q19") (pin "2") (pinfunction "D_2") (pintype "passive"))
      (node (ref "Q20") (pin "2") (pinfunction "D_2") (pintype "passive"))
      (node (ref "Q21") (pin "2") (pinfunction "D_2") (pintype "passive"))
    )
    (net (code "22") (name "/DRAIN_AL") (class "Default")
      (node (ref "C54") (pin "2") (pinfunction "2_2") (pintype "passive"))
      (node (ref "C57") (pin "2") (pinfunction "2_2") (pintype "passive"))
      (node (ref "C58") (pin "2") (pinfunction "2_2") (pintype "passive"))
      (node (ref "C66") (pin "2") (pinfunction "2_2") (pintype "passive"))
      (node (ref "C67") (pin "2") (pinfunction "2_2") (pintype "passive"))
      (node (ref "C73") (pin "1") (pinfunction "1_1") (pintype "passive"))
      (node (ref "C74") (pin "1") (pinfunction "1_1") (pintype "passive"))
      (node (ref "C81") (pin "1") (pinfunction "1_1") (pintype "passive"))
      (node (ref "C82") (pin "1") (pinfunction "1_1") (pintype "passive"))
      (node (ref "D15") (pin "1") (pinfunction "Cathode_1") (pintype "passive"))
      (node (ref "D8") (pin "2") (pinfunction "Anode_2") (pintype "passive"))
      (node (ref "IC14") (pin "1") (pinfunction "IN_1_1") (pintype "passive"))
      (node (ref "IC14") (pin "2") (pinfunction "IN_2_2") (pintype "passive"))
      (node (ref "IC14") (pin "3") (pinfunction "IN_3_3") (pintype "passive"))
      (node (ref "IC7") (pin "3") (pinfunction "GND2_3") (pintype "passive"))
      (node (ref "Q19") (pin "3") (pinfunction "S_3") (pintype "passive"))
      (node (ref "Q20") (pin "3") (pinfunction "S_3") (pintype "passive"))
      (node (ref "Q21") (pin "3") (pinfunction "S_3") (pintype "passive"))
      (node (ref "Q28") (pin "2") (pinfunction "D_2") (pintype "passive"))
      (node (ref "Q29") (pin "2") (pinfunction "D_2") (pintype "passive"))
      (node (ref "Q30") (pin "2") (pinfunction "D_2") (pintype "passive"))
    )
    (net (code "23") (name "/DRAIN_BL") (class "Default")
      (node (ref "C55") (pin "2") (pinfunction "2_2") (pintype "passive"))
      (node (ref "C59") (pin "2") (pinfunction "2_2") (pintype "passive"))
      (node (ref "C60") (pin "2") (pinfunction "2_2") (pintype "passive"))
      (node (ref "C68") (pin "2") (pinfunction "2_2") (pintype "passive"))
      (node (ref "C69") (pin "2") (pinfunction "2_2") (pintype "passive"))
      (node (ref "C77") (pin "1") (pinfunction "1_1") (pintype "passive"))
      (node (ref "C78") (pin "1") (pinfunction "1_1") (pintype "passive"))
      (node (ref "C83") (pin "1") (pinfunction "1_1") (pintype "passive"))
      (node (ref "C84") (pin "1") (pinfunction "1_1") (pintype "passive"))
      (node (ref "D17") (pin "1") (pinfunction "Cathode_1") (pintype "passive"))
      (node (ref "D9") (pin "2") (pinfunction "Anode_2") (pintype "passive"))
      (node (ref "IC12") (pin "1") (pinfunction "IN_1_1") (pintype "passive"))
      (node (ref "IC12") (pin "2") (pinfunction "IN_2_2") (pintype "passive"))
      (node (ref "IC12") (pin "3") (pinfunction "IN_3_3") (pintype "passive"))
      (node (ref "IC8") (pin "3") (pinfunction "GND2_3") (pintype "passive"))
      (node (ref "Q13") (pin "3") (pinfunction "S_3") (pintype "passive"))
      (node (ref "Q14") (pin "3") (pinfunction "S_3") (pintype "passive"))
      (node (ref "Q15") (pin "3") (pinfunction "S_3") (pintype "passive"))
      (node (ref "Q22") (pin "2") (pinfunction "D_2") (pintype "passive"))
      (node (ref "Q23") (pin "2") (pinfunction "D_2") (pintype "passive"))
      (node (ref "Q24") (pin "2") (pinfunction "D_2") (pintype "passive"))
    )
    (net (code "24") (name "/DRAIN_CL") (class "Default")
      (node (ref "C56") (pin "2") (pinfunction "2_2") (pintype "passive"))
      (node (ref "C61") (pin "2") (pinfunction "2_2") (pintype "passive"))
      (node (ref "C62") (pin "2") (pinfunction "2_2") (pintype "passive"))
      (node (ref "C70") (pin "2") (pinfunction "2_2") (pintype "passive"))
      (node (ref "C71") (pin "2") (pinfunction "2_2") (pintype "passive"))
      (node (ref "C79") (pin "1") (pinfunction "1_1") (pintype "passive"))
      (node (ref "C80") (pin "1") (pinfunction "1_1") (pintype "passive"))
      (node (ref "C85") (pin "1") (pinfunction "1_1") (pintype "passive"))
      (node (ref "C86") (pin "1") (pinfunction "1_1") (pintype "passive"))
      (node (ref "D10") (pin "2") (pinfunction "Anode_2") (pintype "passive"))
      (node (ref "D19") (pin "1") (pinfunction "Cathode_1") (pintype "passive"))
      (node (ref "IC13") (pin "1") (pinfunction "IN_1_1") (pintype "passive"))
      (node (ref "IC13") (pin "2") (pinfunction "IN_2_2") (pintype "passive"))
      (node (ref "IC13") (pin "3") (pinfunction "IN_3_3") (pintype "passive"))
      (node (ref "IC6") (pin "3") (pinfunction "GND2_3") (pintype "passive"))
      (node (ref "Q16") (pin "3") (pinfunction "S_3") (pintype "passive"))
      (node (ref "Q17") (pin "3") (pinfunction "S_3") (pintype "passive"))
      (node (ref "Q18") (pin "3") (pinfunction "S_3") (pintype "passive"))
      (node (ref "Q25") (pin "2") (pinfunction "D_2") (pintype "passive"))
      (node (ref "Q26") (pin "2") (pinfunction "D_2") (pintype "passive"))
      (node (ref "Q27") (pin "2") (pinfunction "D_2") (pintype "passive"))
    )
    (net (code "25") (name "/GATE_AH") (class "Default")
      (node (ref "D11") (pin "2") (pinfunction "Anode_2") (pintype "passive"))
      (node (ref "R57") (pin "2") (pinfunction "2_2") (pintype "passive"))
      (node (ref "R66") (pin "2") (pinfunction "2_2") (pintype "passive"))
      (node (ref "R93") (pin "1") (pinfunction "1_1") (pintype "passive"))
      (node (ref "R94") (pin "1") (pinfunction "1_1") (pintype "passive"))
      (node (ref "R95") (pin "1") (pinfunction "1_1") (pintype "passive"))
    )
    (net (code "26") (name "/GATE_AL") (class "Default")
      (node (ref "D23") (pin "2") (pinfunction "Anode_2") (pintype "passive"))
      (node (ref "R102") (pin "1") (pinfunction "1_1") (pintype "passive"))
      (node (ref "R103") (pin "1") (pinfunction "1_1") (pintype "passive"))
      (node (ref "R104") (pin "1") (pinfunction "1_1") (pintype "passive"))
      (node (ref "R72") (pin "2") (pinfunction "2_2") (pintype "passive"))
      (node (ref "R81") (pin "2") (pinfunction "2_2") (pintype "passive"))
    )
    (net (code "27") (name "/GATE_BH") (class "Default")
      (node (ref "D12") (pin "2") (pinfunction "Anode_2") (pintype "passive"))
      (node (ref "R58") (pin "2") (pinfunction "2_2") (pintype "passive"))
      (node (ref "R67") (pin "2") (pinfunction "2_2") (pintype "passive"))
      (node (ref "R86") (pin "1") (pinfunction "1_1") (pintype "passive"))
      (node (ref "R87") (pin "1") (pinfunction "1_1") (pintype "passive"))
      (node (ref "R88") (pin "1") (pinfunction "1_1") (pintype "passive"))
    )
    (net (code "28") (name "/GATE_BL") (class "Default")
      (node (ref "D24") (pin "2") (pinfunction "Anode_2") (pintype "passive"))
      (node (ref "R73") (pin "2") (pinfunction "2_2") (pintype "passive"))
      (node (ref "R82") (pin "2") (pinfunction "2_2") (pintype "passive"))
      (node (ref "R96") (pin "1") (pinfunction "1_1") (pintype "passive"))
      (node (ref "R97") (pin "1") (pinfunction "1_1") (pintype "passive"))
      (node (ref "R98") (pin "1") (pinfunction "1_1") (pintype "passive"))
    )
    (net (code "29") (name "/GATE_CH") (class "Default")
      (node (ref "D13") (pin "2") (pinfunction "Anode_2") (pintype "passive"))
      (node (ref "R59") (pin "2") (pinfunction "2_2") (pintype "passive"))
      (node (ref "R68") (pin "2") (pinfunction "2_2") (pintype "passive"))
      (node (ref "R90") (pin "1") (pinfunction "1_1") (pintype "passive"))
      (node (ref "R91") (pin "1") (pinfunction "1_1") (pintype "passive"))
      (node (ref "R92") (pin "1") (pinfunction "1_1") (pintype "passive"))
    )
    (net (code "30") (name "/GATE_CL") (class "Default")
      (node (ref "D25") (pin "2") (pinfunction "Anode_2") (pintype "passive"))
      (node (ref "R100") (pin "1") (pinfunction "1_1") (pintype "passive"))
      (node (ref "R101") (pin "1") (pinfunction "1_1") (pintype "passive"))
      (node (ref "R74") (pin "2") (pinfunction "2_2") (pintype "passive"))
      (node (ref "R83") (pin "2") (pinfunction "2_2") (pintype "passive"))
      (node (ref "R99") (pin "1") (pinfunction "1_1") (pintype "passive"))
    )
    (net (code "31") (name "/GD_RESET_FILT-A") (class "Default")
      (node (ref "IC10") (pin "14") (pinfunction "/RST_14") (pintype "passive"))
      (node (ref "IC7") (pin "14") (pinfunction "/RST_14") (pintype "passive"))
    )
    (net (code "32") (name "/GD_RESET_FILT-B") (class "Default")
      (node (ref "IC11") (pin "14") (pinfunction "/RST_14") (pintype "passive"))
      (node (ref "IC8") (pin "14") (pinfunction "/RST_14") (pintype "passive"))
    )
    (net (code "33") (name "/GD_RESET_FILT-C") (class "Default")
      (node (ref "IC15") (pin "14") (pinfunction "/RST_14") (pintype "passive"))
      (node (ref "IC6") (pin "14") (pinfunction "/RST_14") (pintype "passive"))
    )
    (net (code "34") (name "/IA_CSensor") (class "Default")
      (node (ref "IC14") (pin "OUT") (pinfunction "OUT_OUT") (pintype "passive"))
    )
    (net (code "35") (name "/IB_CSensor") (class "Default")
      (node (ref "IC12") (pin "OUT") (pinfunction "OUT_OUT") (pintype "passive"))
    )
    (net (code "36") (name "/IC_CSensor") (class "Default")
      (node (ref "IC13") (pin "OUT") (pinfunction "OUT_OUT") (pintype "passive"))
    )
    (net (code "37") (name "/M_A") (class "Default")
      (node (ref "IC14") (pin "4") (pinfunction "OUT_4_4") (pintype "passive"))
      (node (ref "IC14") (pin "5") (pinfunction "OUT_5_5") (pintype "passive"))
      (node (ref "IC14") (pin "6") (pinfunction "OUT_6_6") (pintype "passive"))
      (node (ref "J7") (pin "1") (pinfunction "1_1") (pintype "passive"))
    )
    (net (code "38") (name "/M_B") (class "Default")
      (node (ref "IC12") (pin "4") (pinfunction "OUT_4_4") (pintype "passive"))
      (node (ref "IC12") (pin "5") (pinfunction "OUT_5_5") (pintype "passive"))
      (node (ref "IC12") (pin "6") (pinfunction "OUT_6_6") (pintype "passive"))
      (node (ref "J9") (pin "1") (pinfunction "1_1") (pintype "passive"))
    )
    (net (code "39") (name "/M_C") (class "Default")
      (node (ref "IC13") (pin "4") (pinfunction "OUT_4_4") (pintype "passive"))
      (node (ref "IC13") (pin "5") (pinfunction "OUT_5_5") (pintype "passive"))
      (node (ref "IC13") (pin "6") (pinfunction "OUT_6_6") (pintype "passive"))
      (node (ref "J8") (pin "1") (pinfunction "1_1") (pintype "passive"))
    )
    (net (code "40") (name "/V-") (class "Default")
      (node (ref "C100") (pin "2") (pinfunction "2_2") (pintype "passive"))
      (node (ref "C101") (pin "2") (pinfunction "2_2") (pintype "passive"))
      (node (ref "C102") (pin "2") (pinfunction "2_2") (pintype "passive"))
      (node (ref "C103") (pin "2") (pinfunction "2_2") (pintype "passive"))
      (node (ref "C104") (pin "2") (pinfunction "2_2") (pintype "passive"))
      (node (ref "C106") (pin "1") (pinfunction "1_1") (pintype "passive"))
      (node (ref "C107") (pin "1") (pinfunction "1_1") (pintype "passive"))
      (node (ref "C110") (pin "1") (pinfunction "1_1") (pintype "passive"))
      (node (ref "C111") (pin "1") (pinfunction "1_1") (pintype "passive"))
      (node (ref "C112") (pin "1") (pinfunction "1_1") (pintype "passive"))
      (node (ref "C113") (pin "1") (pinfunction "1_1") (pintype "passive"))
      (node (ref "C114") (pin "1") (pinfunction "1_1") (pintype "passive"))
      (node (ref "C115") (pin "1") (pinfunction "1_1") (pintype "passive"))
      (node (ref "C116") (pin "1") (pinfunction "1_1") (pintype "passive"))
      (node (ref "C117") (pin "1") (pinfunction "1_1") (pintype "passive"))
      (node (ref "C118") (pin "1") (pinfunction "1_1") (pintype "passive"))
      (node (ref "C119") (pin "1") (pinfunction "1_1") (pintype "passive"))
      (node (ref "C87") (pin "2") (pinfunction "2_2") (pintype "passive"))
      (node (ref "C88") (pin "2") (pinfunction "2_2") (pintype "passive"))
      (node (ref "C89") (pin "2") (pinfunction "2_2") (pintype "passive"))
      (node (ref "C90") (pin "2") (pinfunction "2_2") (pintype "passive"))
      (node (ref "C91") (pin "2") (pinfunction "2_2") (pintype "passive"))
      (node (ref "C92") (pin "2") (pinfunction "2_2") (pintype "passive"))
      (node (ref "C93") (pin "2") (pinfunction "2_2") (pintype "passive"))
      (node (ref "C94") (pin "2") (pinfunction "2_2") (pintype "passive"))
      (node (ref "C95") (pin "2") (pinfunction "2_2") (pintype "passive"))
      (node (ref "C99") (pin "2") (pinfunction "2_2") (pintype "passive"))
      (node (ref "D20") (pin "2") (pinfunction "Anode_2") (pintype "passive"))
      (node (ref "D21") (pin "2") (pinfunction "Anode_2") (pintype "passive"))
      (node (ref "D22") (pin "2") (pinfunction "Anode_2") (pintype "passive"))
      (node (ref "IC10") (pin "3") (pinfunction "GND2_3") (pintype "passive"))
      (node (ref "IC11") (pin "3") (pinfunction "GND2_3") (pintype "passive"))
      (node (ref "IC15") (pin "3") (pinfunction "GND2_3") (pintype "passive"))
      (node (ref "Q22") (pin "3") (pinfunction "S_3") (pintype "passive"))
      (node (ref "Q23") (pin "3") (pinfunction "S_3") (pintype "passive"))
      (node (ref "Q24") (pin "3") (pinfunction "S_3") (pintype "passive"))
      (node (ref "Q25") (pin "3") (pinfunction "S_3") (pintype "passive"))
      (node (ref "Q26") (pin "3") (pinfunction "S_3") (pintype "passive"))
      (node (ref "Q27") (pin "3") (pinfunction "S_3") (pintype "passive"))
      (node (ref "Q28") (pin "3") (pinfunction "S_3") (pintype "passive"))
      (node (ref "Q29") (pin "3") (pinfunction "S_3") (pintype "passive"))
      (node (ref "Q30") (pin "3") (pinfunction "S_3") (pintype "passive"))
    )
    (net (code "41") (name "/VN_AH") (class "Default")
      (node (ref "C63") (pin "1") (pinfunction "1_1") (pintype "passive"))
      (node (ref "C73") (pin "2") (pinfunction "2_2") (pintype "passive"))
      (node (ref "C74") (pin "2") (pinfunction "2_2") (pintype "passive"))
      (node (ref "C81") (pin "2") (pinfunction "2_2") (pintype "passive"))
      (node (ref "C82") (pin "2") (pinfunction "2_2") (pintype "passive"))
      (node (ref "IC7") (pin "1") (pinfunction "VEE2_1") (pintype "passive"))
      (node (ref "IC7") (pin "8") (pinfunction "VEE2_8") (pintype "passive"))
      (node (ref "Q4") (pin "3") (pinfunction "C_3") (pintype "passive"))
    )
    (net (code "42") (name "/VN_AL") (class "Default")
      (node (ref "C106") (pin "2") (pinfunction "2_2") (pintype "passive"))
      (node (ref "C107") (pin "2") (pinfunction "2_2") (pintype "passive"))
      (node (ref "C114") (pin "2") (pinfunction "2_2") (pintype "passive"))
      (node (ref "C115") (pin "2") (pinfunction "2_2") (pintype "passive"))
      (node (ref "C96") (pin "1") (pinfunction "1_1") (pintype "passive"))
      (node (ref "IC10") (pin "1") (pinfunction "VEE2_1") (pintype "passive"))
      (node (ref "IC10") (pin "8") (pinfunction "VEE2_8") (pintype "passive"))
      (node (ref "Q10") (pin "3") (pinfunction "C_3") (pintype "passive"))
    )
    (net (code "43") (name "/VN_BH") (class "Default")
      (node (ref "C64") (pin "1") (pinfunction "1_1") (pintype "passive"))
      (node (ref "C77") (pin "2") (pinfunction "2_2") (pintype "passive"))
      (node (ref "C78") (pin "2") (pinfunction "2_2") (pintype "passive"))
      (node (ref "C83") (pin "2") (pinfunction "2_2") (pintype "passive"))
      (node (ref "C84") (pin "2") (pinfunction "2_2") (pintype "passive"))
      (node (ref "IC8") (pin "1") (pinfunction "VEE2_1") (pintype "passive"))
      (node (ref "IC8") (pin "8") (pinfunction "VEE2_8") (pintype "passive"))
      (node (ref "Q5") (pin "3") (pinfunction "C_3") (pintype "passive"))
    )
    (net (code "44") (name "/VN_BL") (class "Default")
      (node (ref "C110") (pin "2") (pinfunction "2_2") (pintype "passive"))
      (node (ref "C111") (pin "2") (pinfunction "2_2") (pintype "passive"))
      (node (ref "C116") (pin "2") (pinfunction "2_2") (pintype "passive"))
      (node (ref "C117") (pin "2") (pinfunction "2_2") (pintype "passive"))
      (node (ref "C97") (pin "1") (pinfunction "1_1") (pintype "passive"))
      (node (ref "IC11") (pin "1") (pinfunction "VEE2_1") (pintype "passive"))
      (node (ref "IC11") (pin "8") (pinfunction "VEE2_8") (pintype "passive"))
      (node (ref "Q11") (pin "3") (pinfunction "C_3") (pintype "passive"))
    )
    (net (code "45") (name "/VN_CH") (class "Default")
      (node (ref "C65") (pin "1") (pinfunction "1_1") (pintype "passive"))
      (node (ref "C79") (pin "2") (pinfunction "2_2") (pintype "passive"))
      (node (ref "C80") (pin "2") (pinfunction "2_2") (pintype "passive"))
      (node (ref "C85") (pin "2") (pinfunction "2_2") (pintype "passive"))
      (node (ref "C86") (pin "2") (pinfunction "2_2") (pintype "passive"))
      (node (ref "IC6") (pin "1") (pinfunction "VEE2_1") (pintype "passive"))
      (node (ref "IC6") (pin "8") (pinfunction "VEE2_8") (pintype "passive"))
      (node (ref "Q6") (pin "3") (pinfunction "C_3") (pintype "passive"))
    )
    (net (code "46") (name "/VN_CL") (class "Default")
      (node (ref "C112") (pin "2") (pinfunction "2_2") (pintype "passive"))
      (node (ref "C113") (pin "2") (pinfunction "2_2") (pintype "passive"))
      (node (ref "C118") (pin "2") (pinfunction "2_2") (pintype "passive"))
      (node (ref "C119") (pin "2") (pinfunction "2_2") (pintype "passive"))
      (node (ref "C98") (pin "1") (pinfunction "1_1") (pintype "passive"))
      (node (ref "IC15") (pin "1") (pinfunction "VEE2_1") (pintype "passive"))
      (node (ref "IC15") (pin "8") (pinfunction "VEE2_8") (pintype "passive"))
      (node (ref "Q12") (pin "3") (pinfunction "C_3") (pintype "passive"))
    )
    (net (code "47") (name "/VP_AH") (class "Default")
      (node (ref "C57") (pin "1") (pinfunction "1_1") (pintype "passive"))
      (node (ref "C58") (pin "1") (pinfunction "1_1") (pintype "passive"))
      (node (ref "C63") (pin "2") (pinfunction "2_2") (pintype "passive"))
      (node (ref "C66") (pin "1") (pinfunction "1_1") (pintype "passive"))
      (node (ref "C67") (pin "1") (pinfunction "1_1") (pintype "passive"))
      (node (ref "D11") (pin "1") (pinfunction "Cathode_1") (pintype "passive"))
      (node (ref "IC7") (pin "5") (pinfunction "VCC2_5") (pintype "passive"))
      (node (ref "Q1") (pin "3") (pinfunction "C_3") (pintype "passive"))
    )
    (net (code "48") (name "/VP_AL") (class "Default")
      (node (ref "C100") (pin "1") (pinfunction "1_1") (pintype "passive"))
      (node (ref "C90") (pin "1") (pinfunction "1_1") (pintype "passive"))
      (node (ref "C91") (pin "1") (pinfunction "1_1") (pintype "passive"))
      (node (ref "C96") (pin "2") (pinfunction "2_2") (pintype "passive"))
      (node (ref "C99") (pin "1") (pinfunction "1_1") (pintype "passive"))
      (node (ref "D23") (pin "1") (pinfunction "Cathode_1") (pintype "passive"))
      (node (ref "IC10") (pin "5") (pinfunction "VCC2_5") (pintype "passive"))
      (node (ref "Q7") (pin "3") (pinfunction "C_3") (pintype "passive"))
    )
    (net (code "49") (name "/VP_BH") (class "Default")
      (node (ref "C59") (pin "1") (pinfunction "1_1") (pintype "passive"))
      (node (ref "C60") (pin "1") (pinfunction "1_1") (pintype "passive"))
      (node (ref "C64") (pin "2") (pinfunction "2_2") (pintype "passive"))
      (node (ref "C68") (pin "1") (pinfunction "1_1") (pintype "passive"))
      (node (ref "C69") (pin "1") (pinfunction "1_1") (pintype "passive"))
      (node (ref "D12") (pin "1") (pinfunction "Cathode_1") (pintype "passive"))
      (node (ref "IC8") (pin "5") (pinfunction "VCC2_5") (pintype "passive"))
      (node (ref "Q2") (pin "3") (pinfunction "C_3") (pintype "passive"))
    )
    (net (code "50") (name "/VP_BL") (class "Default")
      (node (ref "C101") (pin "1") (pinfunction "1_1") (pintype "passive"))
      (node (ref "C102") (pin "1") (pinfunction "1_1") (pintype "passive"))
      (node (ref "C92") (pin "1") (pinfunction "1_1") (pintype "passive"))
      (node (ref "C93") (pin "1") (pinfunction "1_1") (pintype "passive"))
      (node (ref "C97") (pin "2") (pinfunction "2_2") (pintype "passive"))
      (node (ref "D24") (pin "1") (pinfunction "Cathode_1") (pintype "passive"))
      (node (ref "IC11") (pin "5") (pinfunction "VCC2_5") (pintype "passive"))
      (node (ref "Q8") (pin "3") (pinfunction "C_3") (pintype "passive"))
    )
    (net (code "51") (name "/VP_CH") (class "Default")
      (node (ref "C61") (pin "1") (pinfunction "1_1") (pintype "passive"))
      (node (ref "C62") (pin "1") (pinfunction "1_1") (pintype "passive"))
      (node (ref "C65") (pin "2") (pinfunction "2_2") (pintype "passive"))
      (node (ref "C70") (pin "1") (pinfunction "1_1") (pintype "passive"))
      (node (ref "C71") (pin "1") (pinfunction "1_1") (pintype "passive"))
      (node (ref "D13") (pin "1") (pinfunction "Cathode_1") (pintype "passive"))
      (node (ref "IC6") (pin "5") (pinfunction "VCC2_5") (pintype "passive"))
      (node (ref "Q3") (pin "3") (pinfunction "C_3") (pintype "passive"))
    )
    (net (code "52") (name "/VP_CL") (class "Default")
      (node (ref "C103") (pin "1") (pinfunction "1_1") (pintype "passive"))
      (node (ref "C104") (pin "1") (pinfunction "1_1") (pintype "passive"))
      (node (ref "C94") (pin "1") (pinfunction "1_1") (pintype "passive"))
      (node (ref "C95") (pin "1") (pinfunction "1_1") (pintype "passive"))
      (node (ref "C98") (pin "2") (pinfunction "2_2") (pintype "passive"))
      (node (ref "D25") (pin "1") (pinfunction "Cathode_1") (pintype "passive"))
      (node (ref "IC15") (pin "5") (pinfunction "VCC2_5") (pintype "passive"))
      (node (ref "Q9") (pin "3") (pinfunction "C_3") (pintype "passive"))
    )
    (net (code "53") (name "GND_CURRENTSENS") (class "Default")
      (node (ref "C120") (pin "2") (pinfunction "2_2") (pintype "passive"))
      (node (ref "C121") (pin "2") (pinfunction "2_2") (pintype "passive"))
      (node (ref "C122") (pin "2") (pinfunction "2_2") (pintype "passive"))
      (node (ref "IC12") (pin "0V") (pinfunction "0V_0V") (pintype "power_in"))
      (node (ref "IC13") (pin "0V") (pinfunction "0V_0V") (pintype "power_in"))
      (node (ref "IC14") (pin "0V") (pinfunction "0V_0V") (pintype "power_in"))
    )
    (net (code "54") (name "GND_Cntrl") (class "Default")
      (node (ref "C105") (pin "2") (pinfunction "2_2") (pintype "passive"))
      (node (ref "C108") (pin "2") (pinfunction "2_2") (pintype "passive"))
      (node (ref "C109") (pin "2") (pinfunction "2_2") (pintype "passive"))
      (node (ref "C72") (pin "2") (pinfunction "2_2") (pintype "passive"))
      (node (ref "C75") (pin "2") (pinfunction "2_2") (pintype "passive"))
      (node (ref "C76") (pin "2") (pinfunction "2_2") (pintype "passive"))
      (node (ref "IC10") (pin "11") (pinfunction "IN-_11") (pintype "passive"))
      (node (ref "IC10") (pin "16") (pinfunction "GND1_16") (pintype "passive"))
      (node (ref "IC10") (pin "9") (pinfunction "GND1_9") (pintype "passive"))
      (node (ref "IC11") (pin "11") (pinfunction "IN-_11") (pintype "passive"))
      (node (ref "IC11") (pin "16") (pinfunction "GND1_16") (pintype "passive"))
      (node (ref "IC11") (pin "9") (pinfunction "GND1_9") (pintype "passive"))
      (node (ref "IC15") (pin "11") (pinfunction "IN-_11") (pintype "passive"))
      (node (ref "IC15") (pin "16") (pinfunction "GND1_16") (pintype "passive"))
      (node (ref "IC15") (pin "9") (pinfunction "GND1_9") (pintype "passive"))
      (node (ref "IC6") (pin "11") (pinfunction "IN-_11") (pintype "passive"))
      (node (ref "IC6") (pin "16") (pinfunction "GND1_16") (pintype "passive"))
      (node (ref "IC6") (pin "9") (pinfunction "GND1_9") (pintype "passive"))
      (node (ref "IC7") (pin "11") (pinfunction "IN-_11") (pintype "passive"))
      (node (ref "IC7") (pin "16") (pinfunction "GND1_16") (pintype "passive"))
      (node (ref "IC7") (pin "9") (pinfunction "GND1_9") (pintype "passive"))
      (node (ref "IC8") (pin "11") (pinfunction "IN-_11") (pintype "passive"))
      (node (ref "IC8") (pin "16") (pinfunction "GND1_16") (pintype "passive"))
      (node (ref "IC8") (pin "9") (pinfunction "GND1_9") (pintype "passive"))
    )
    (net (code "55") (name "Net-(D2-Anode)") (class "Default")
      (node (ref "D2") (pin "2") (pinfunction "Anode_2") (pintype "passive"))
      (node (ref "D3") (pin "2") (pinfunction "Anode_2") (pintype "passive"))
    )
    (net (code "56") (name "Net-(D2-Cathode)") (class "Default")
      (node (ref "D2") (pin "1") (pinfunction "Cathode_1") (pintype "passive"))
      (node (ref "R54") (pin "2") (pinfunction "2_2") (pintype "passive"))
    )
    (net (code "57") (name "Net-(D4-Anode)") (class "Default")
      (node (ref "D4") (pin "2") (pinfunction "Anode_2") (pintype "passive"))
      (node (ref "D5") (pin "2") (pinfunction "Anode_2") (pintype "passive"))
    )
    (net (code "58") (name "Net-(D4-Cathode)") (class "Default")
      (node (ref "D4") (pin "1") (pinfunction "Cathode_1") (pintype "passive"))
      (node (ref "R55") (pin "2") (pinfunction "2_2") (pintype "passive"))
    )
    (net (code "59") (name "Net-(D6-Anode)") (class "Default")
      (node (ref "D6") (pin "2") (pinfunction "Anode_2") (pintype "passive"))
      (node (ref "D7") (pin "2") (pinfunction "Anode_2") (pintype "passive"))
    )
    (net (code "60") (name "Net-(D6-Cathode)") (class "Default")
      (node (ref "D6") (pin "1") (pinfunction "Cathode_1") (pintype "passive"))
      (node (ref "R56") (pin "2") (pinfunction "2_2") (pintype "passive"))
    )
    (net (code "61") (name "Net-(D8-Cathode)") (class "Default")
      (node (ref "C54") (pin "1") (pinfunction "1_1") (pintype "passive"))
      (node (ref "D8") (pin "1") (pinfunction "Cathode_1") (pintype "passive"))
      (node (ref "IC7") (pin "2") (pinfunction "DESAT_2") (pintype "passive"))
      (node (ref "R54") (pin "1") (pinfunction "1_1") (pintype "passive"))
    )
    (net (code "62") (name "Net-(D9-Cathode)") (class "Default")
      (node (ref "C55") (pin "1") (pinfunction "1_1") (pintype "passive"))
      (node (ref "D9") (pin "1") (pinfunction "Cathode_1") (pintype "passive"))
      (node (ref "IC8") (pin "2") (pinfunction "DESAT_2") (pintype "passive"))
      (node (ref "R55") (pin "1") (pinfunction "1_1") (pintype "passive"))
    )
    (net (code "63") (name "Net-(D10-Cathode)") (class "Default")
      (node (ref "C56") (pin "1") (pinfunction "1_1") (pintype "passive"))
      (node (ref "D10") (pin "1") (pinfunction "Cathode_1") (pintype "passive"))
      (node (ref "IC6") (pin "2") (pinfunction "DESAT_2") (pintype "passive"))
      (node (ref "R56") (pin "1") (pinfunction "1_1") (pintype "passive"))
    )
    (net (code "64") (name "Net-(D14-Anode)") (class "Default")
      (node (ref "D14") (pin "2") (pinfunction "Anode_2") (pintype "passive"))
      (node (ref "D15") (pin "2") (pinfunction "Anode_2") (pintype "passive"))
    )
    (net (code "65") (name "Net-(D14-Cathode)") (class "Default")
      (node (ref "D14") (pin "1") (pinfunction "Cathode_1") (pintype "passive"))
      (node (ref "R69") (pin "2") (pinfunction "2_2") (pintype "passive"))
    )
    (net (code "66") (name "Net-(D16-Anode)") (class "Default")
      (node (ref "D16") (pin "2") (pinfunction "Anode_2") (pintype "passive"))
      (node (ref "D17") (pin "2") (pinfunction "Anode_2") (pintype "passive"))
    )
    (net (code "67") (name "Net-(D16-Cathode)") (class "Default")
      (node (ref "D16") (pin "1") (pinfunction "Cathode_1") (pintype "passive"))
      (node (ref "R70") (pin "2") (pinfunction "2_2") (pintype "passive"))
    )
    (net (code "68") (name "Net-(D18-Anode)") (class "Default")
      (node (ref "D18") (pin "2") (pinfunction "Anode_2") (pintype "passive"))
      (node (ref "D19") (pin "2") (pinfunction "Anode_2") (pintype "passive"))
    )
    (net (code "69") (name "Net-(D18-Cathode)") (class "Default")
      (node (ref "D18") (pin "1") (pinfunction "Cathode_1") (pintype "passive"))
      (node (ref "R71") (pin "2") (pinfunction "2_2") (pintype "passive"))
    )
    (net (code "70") (name "Net-(D20-Cathode)") (class "Default")
      (node (ref "C87") (pin "1") (pinfunction "1_1") (pintype "passive"))
      (node (ref "D20") (pin "1") (pinfunction "Cathode_1") (pintype "passive"))
      (node (ref "IC10") (pin "2") (pinfunction "DESAT_2") (pintype "passive"))
      (node (ref "R69") (pin "1") (pinfunction "1_1") (pintype "passive"))
    )
    (net (code "71") (name "Net-(D21-Cathode)") (class "Default")
      (node (ref "C88") (pin "1") (pinfunction "1_1") (pintype "passive"))
      (node (ref "D21") (pin "1") (pinfunction "Cathode_1") (pintype "passive"))
      (node (ref "IC11") (pin "2") (pinfunction "DESAT_2") (pintype "passive"))
      (node (ref "R70") (pin "1") (pinfunction "1_1") (pintype "passive"))
    )
    (net (code "72") (name "Net-(D22-Cathode)") (class "Default")
      (node (ref "C89") (pin "1") (pinfunction "1_1") (pintype "passive"))
      (node (ref "D22") (pin "1") (pinfunction "Cathode_1") (pintype "passive"))
      (node (ref "IC15") (pin "2") (pinfunction "DESAT_2") (pintype "passive"))
      (node (ref "R71") (pin "1") (pinfunction "1_1") (pintype "passive"))
    )
    (net (code "73") (name "Net-(IC6-OUT)") (class "Default")
      (node (ref "IC6") (pin "6") (pinfunction "OUT_6") (pintype "passive"))
      (node (ref "R64") (pin "1") (pinfunction "1_1") (pintype "passive"))
    )
    (net (code "74") (name "Net-(IC7-OUT)") (class "Default")
      (node (ref "IC7") (pin "6") (pinfunction "OUT_6") (pintype "passive"))
      (node (ref "R60") (pin "1") (pinfunction "1_1") (pintype "passive"))
    )
    (net (code "75") (name "Net-(IC8-OUT)") (class "Default")
      (node (ref "IC8") (pin "6") (pinfunction "OUT_6") (pintype "passive"))
      (node (ref "R62") (pin "1") (pinfunction "1_1") (pintype "passive"))
    )
    (net (code "76") (name "Net-(IC10-OUT)") (class "Default")
      (node (ref "IC10") (pin "6") (pinfunction "OUT_6") (pintype "passive"))
      (node (ref "R75") (pin "1") (pinfunction "1_1") (pintype "passive"))
    )
    (net (code "77") (name "Net-(IC11-OUT)") (class "Default")
      (node (ref "IC11") (pin "6") (pinfunction "OUT_6") (pintype "passive"))
      (node (ref "R77") (pin "1") (pinfunction "1_1") (pintype "passive"))
    )
    (net (code "78") (name "Net-(IC15-OUT)") (class "Default")
      (node (ref "IC15") (pin "6") (pinfunction "OUT_6") (pintype "passive"))
      (node (ref "R79") (pin "1") (pinfunction "1_1") (pintype "passive"))
    )
    (net (code "79") (name "Net-(Q1-B)") (class "Default")
      (node (ref "Q1") (pin "1") (pinfunction "B_1") (pintype "passive"))
      (node (ref "Q4") (pin "1") (pinfunction "B_1") (pintype "passive"))
      (node (ref "R60") (pin "2") (pinfunction "2_2") (pintype "passive"))
      (node (ref "R61") (pin "1") (pinfunction "1_1") (pintype "passive"))
    )
    (net (code "80") (name "Net-(Q1-E)") (class "Default")
      (node (ref "Q1") (pin "2") (pinfunction "E_2") (pintype "passive"))
      (node (ref "Q4") (pin "2") (pinfunction "E_2") (pintype "passive"))
      (node (ref "R57") (pin "1") (pinfunction "1_1") (pintype "passive"))
      (node (ref "R61") (pin "2") (pinfunction "2_2") (pintype "passive"))
      (node (ref "R66") (pin "1") (pinfunction "1_1") (pintype "passive"))
    )
    (net (code "81") (name "Net-(Q2-B)") (class "Default")
      (node (ref "Q2") (pin "1") (pinfunction "B_1") (pintype "passive"))
      (node (ref "Q5") (pin "1") (pinfunction "B_1") (pintype "passive"))
      (node (ref "R62") (pin "2") (pinfunction "2_2") (pintype "passive"))
      (node (ref "R63") (pin "1") (pinfunction "1_1") (pintype "passive"))
    )
    (net (code "82") (name "Net-(Q2-E)") (class "Default")
      (node (ref "Q2") (pin "2") (pinfunction "E_2") (pintype "passive"))
      (node (ref "Q5") (pin "2") (pinfunction "E_2") (pintype "passive"))
      (node (ref "R58") (pin "1") (pinfunction "1_1") (pintype "passive"))
      (node (ref "R63") (pin "2") (pinfunction "2_2") (pintype "passive"))
      (node (ref "R67") (pin "1") (pinfunction "1_1") (pintype "passive"))
    )
    (net (code "83") (name "Net-(Q3-B)") (class "Default")
      (node (ref "Q3") (pin "1") (pinfunction "B_1") (pintype "passive"))
      (node (ref "Q6") (pin "1") (pinfunction "B_1") (pintype "passive"))
      (node (ref "R64") (pin "2") (pinfunction "2_2") (pintype "passive"))
      (node (ref "R65") (pin "1") (pinfunction "1_1") (pintype "passive"))
    )
    (net (code "84") (name "Net-(Q3-E)") (class "Default")
      (node (ref "Q3") (pin "2") (pinfunction "E_2") (pintype "passive"))
      (node (ref "Q6") (pin "2") (pinfunction "E_2") (pintype "passive"))
      (node (ref "R59") (pin "1") (pinfunction "1_1") (pintype "passive"))
      (node (ref "R65") (pin "2") (pinfunction "2_2") (pintype "passive"))
      (node (ref "R68") (pin "1") (pinfunction "1_1") (pintype "passive"))
    )
    (net (code "85") (name "Net-(Q10-B)") (class "Default")
      (node (ref "Q10") (pin "1") (pinfunction "B_1") (pintype "passive"))
      (node (ref "Q7") (pin "1") (pinfunction "B_1") (pintype "passive"))
      (node (ref "R75") (pin "2") (pinfunction "2_2") (pintype "passive"))
      (node (ref "R76") (pin "1") (pinfunction "1_1") (pintype "passive"))
    )
    (net (code "86") (name "Net-(Q10-E)") (class "Default")
      (node (ref "Q10") (pin "2") (pinfunction "E_2") (pintype "passive"))
      (node (ref "Q7") (pin "2") (pinfunction "E_2") (pintype "passive"))
      (node (ref "R72") (pin "1") (pinfunction "1_1") (pintype "passive"))
      (node (ref "R76") (pin "2") (pinfunction "2_2") (pintype "passive"))
      (node (ref "R81") (pin "1") (pinfunction "1_1") (pintype "passive"))
    )
    (net (code "87") (name "Net-(Q11-B)") (class "Default")
      (node (ref "Q11") (pin "1") (pinfunction "B_1") (pintype "passive"))
      (node (ref "Q8") (pin "1") (pinfunction "B_1") (pintype "passive"))
      (node (ref "R77") (pin "2") (pinfunction "2_2") (pintype "passive"))
      (node (ref "R78") (pin "1") (pinfunction "1_1") (pintype "passive"))
    )
    (net (code "88") (name "Net-(Q11-E)") (class "Default")
      (node (ref "Q11") (pin "2") (pinfunction "E_2") (pintype "passive"))
      (node (ref "Q8") (pin "2") (pinfunction "E_2") (pintype "passive"))
      (node (ref "R73") (pin "1") (pinfunction "1_1") (pintype "passive"))
      (node (ref "R78") (pin "2") (pinfunction "2_2") (pintype "passive"))
      (node (ref "R82") (pin "1") (pinfunction "1_1") (pintype "passive"))
    )
    (net (code "89") (name "Net-(Q12-B)") (class "Default")
      (node (ref "Q12") (pin "1") (pinfunction "B_1") (pintype "passive"))
      (node (ref "Q9") (pin "1") (pinfunction "B_1") (pintype "passive"))
      (node (ref "R79") (pin "2") (pinfunction "2_2") (pintype "passive"))
      (node (ref "R80") (pin "1") (pinfunction "1_1") (pintype "passive"))
    )
    (net (code "90") (name "Net-(Q12-E)") (class "Default")
      (node (ref "Q12") (pin "2") (pinfunction "E_2") (pintype "passive"))
      (node (ref "Q9") (pin "2") (pinfunction "E_2") (pintype "passive"))
      (node (ref "R74") (pin "1") (pinfunction "1_1") (pintype "passive"))
      (node (ref "R80") (pin "2") (pinfunction "2_2") (pintype "passive"))
      (node (ref "R83") (pin "1") (pinfunction "1_1") (pintype "passive"))
    )
    (net (code "91") (name "Net-(Q13-G)") (class "Default")
      (node (ref "Q13") (pin "1") (pinfunction "G_1") (pintype "passive"))
      (node (ref "R86") (pin "2") (pinfunction "2_2") (pintype "passive"))
    )
    (net (code "92") (name "Net-(Q14-G)") (class "Default")
      (node (ref "Q14") (pin "1") (pinfunction "G_1") (pintype "passive"))
      (node (ref "R87") (pin "2") (pinfunction "2_2") (pintype "passive"))
    )
    (net (code "93") (name "Net-(Q15-G)") (class "Default")
      (node (ref "Q15") (pin "1") (pinfunction "G_1") (pintype "passive"))
      (node (ref "R88") (pin "2") (pinfunction "2_2") (pintype "passive"))
    )
    (net (code "94") (name "Net-(Q16-G)") (class "Default")
      (node (ref "Q16") (pin "1") (pinfunction "G_1") (pintype "passive"))
      (node (ref "R90") (pin "2") (pinfunction "2_2") (pintype "passive"))
    )
    (net (code "95") (name "Net-(Q17-G)") (class "Default")
      (node (ref "Q17") (pin "1") (pinfunction "G_1") (pintype "passive"))
      (node (ref "R91") (pin "2") (pinfunction "2_2") (pintype "passive"))
    )
    (net (code "96") (name "Net-(Q18-G)") (class "Default")
      (node (ref "Q18") (pin "1") (pinfunction "G_1") (pintype "passive"))
      (node (ref "R92") (pin "2") (pinfunction "2_2") (pintype "passive"))
    )
    (net (code "97") (name "Net-(Q19-G)") (class "Default")
      (node (ref "Q19") (pin "1") (pinfunction "G_1") (pintype "passive"))
      (node (ref "R93") (pin "2") (pinfunction "2_2") (pintype "passive"))
    )
    (net (code "98") (name "Net-(Q20-G)") (class "Default")
      (node (ref "Q20") (pin "1") (pinfunction "G_1") (pintype "passive"))
      (node (ref "R94") (pin "2") (pinfunction "2_2") (pintype "passive"))
    )
    (net (code "99") (name "Net-(Q21-G)") (class "Default")
      (node (ref "Q21") (pin "1") (pinfunction "G_1") (pintype "passive"))
      (node (ref "R95") (pin "2") (pinfunction "2_2") (pintype "passive"))
    )
    (net (code "100") (name "Net-(Q22-G)") (class "Default")
      (node (ref "Q22") (pin "1") (pinfunction "G_1") (pintype "passive"))
      (node (ref "R96") (pin "2") (pinfunction "2_2") (pintype "passive"))
    )
    (net (code "101") (name "Net-(Q23-G)") (class "Default")
      (node (ref "Q23") (pin "1") (pinfunction "G_1") (pintype "passive"))
      (node (ref "R97") (pin "2") (pinfunction "2_2") (pintype "passive"))
    )
    (net (code "102") (name "Net-(Q24-G)") (class "Default")
      (node (ref "Q24") (pin "1") (pinfunction "G_1") (pintype "passive"))
      (node (ref "R98") (pin "2") (pinfunction "2_2") (pintype "passive"))
    )
    (net (code "103") (name "Net-(Q25-G)") (class "Default")
      (node (ref "Q25") (pin "1") (pinfunction "G_1") (pintype "passive"))
      (node (ref "R99") (pin "2") (pinfunction "2_2") (pintype "passive"))
    )
    (net (code "104") (name "Net-(Q26-G)") (class "Default")
      (node (ref "Q26") (pin "1") (pinfunction "G_1") (pintype "passive"))
      (node (ref "R100") (pin "2") (pinfunction "2_2") (pintype "passive"))
    )
    (net (code "105") (name "Net-(Q27-G)") (class "Default")
      (node (ref "Q27") (pin "1") (pinfunction "G_1") (pintype "passive"))
      (node (ref "R101") (pin "2") (pinfunction "2_2") (pintype "passive"))
    )
    (net (code "106") (name "Net-(Q28-G)") (class "Default")
      (node (ref "Q28") (pin "1") (pinfunction "G_1") (pintype "passive"))
      (node (ref "R102") (pin "2") (pinfunction "2_2") (pintype "passive"))
    )
    (net (code "107") (name "Net-(Q29-G)") (class "Default")
      (node (ref "Q29") (pin "1") (pinfunction "G_1") (pintype "passive"))
      (node (ref "R103") (pin "2") (pinfunction "2_2") (pintype "passive"))
    )
    (net (code "108") (name "Net-(Q30-G)") (class "Default")
      (node (ref "Q30") (pin "1") (pinfunction "G_1") (pintype "passive"))
      (node (ref "R104") (pin "2") (pinfunction "2_2") (pintype "passive"))
    )
    (net (code "109") (name "unconnected-(IC6-CLAMP-Pad7)") (class "Default")
      (node (ref "IC6") (pin "7") (pinfunction "CLAMP_7") (pintype "passive"))
    )
    (net (code "110") (name "unconnected-(IC6-NC-Pad4)") (class "Default")
      (node (ref "IC6") (pin "4") (pinfunction "NC_4") (pintype "passive"))
    )
    (net (code "111") (name "unconnected-(IC7-CLAMP-Pad7)") (class "Default")
      (node (ref "IC7") (pin "7") (pinfunction "CLAMP_7") (pintype "passive"))
    )
    (net (code "112") (name "unconnected-(IC7-NC-Pad4)") (class "Default")
      (node (ref "IC7") (pin "4") (pinfunction "NC_4") (pintype "passive"))
    )
    (net (code "113") (name "unconnected-(IC8-CLAMP-Pad7)") (class "Default")
      (node (ref "IC8") (pin "7") (pinfunction "CLAMP_7") (pintype "passive"))
    )
    (net (code "114") (name "unconnected-(IC8-NC-Pad4)") (class "Default")
      (node (ref "IC8") (pin "4") (pinfunction "NC_4") (pintype "passive"))
    )
    (net (code "115") (name "unconnected-(IC10-CLAMP-Pad7)") (class "Default")
      (node (ref "IC10") (pin "7") (pinfunction "CLAMP_7") (pintype "passive"))
    )
    (net (code "116") (name "unconnected-(IC10-NC-Pad4)") (class "Default")
      (node (ref "IC10") (pin "4") (pinfunction "NC_4") (pintype "passive"))
    )
    (net (code "117") (name "unconnected-(IC11-CLAMP-Pad7)") (class "Default")
      (node (ref "IC11") (pin "7") (pinfunction "CLAMP_7") (pintype "passive"))
    )
    (net (code "118") (name "unconnected-(IC11-NC-Pad4)") (class "Default")
      (node (ref "IC11") (pin "4") (pinfunction "NC_4") (pintype "passive"))
    )
    (net (code "119") (name "unconnected-(IC15-CLAMP-Pad7)") (class "Default")
      (node (ref "IC15") (pin "7") (pinfunction "CLAMP_7") (pintype "passive"))
    )
    (net (code "120") (name "unconnected-(IC15-NC-Pad4)") (class "Default")
      (node (ref "IC15") (pin "4") (pinfunction "NC_4") (pintype "passive"))
    )
  )
)
